# v0_6_stm32-pi.net
KiCad netlist of a schematic drawn in EAGLE
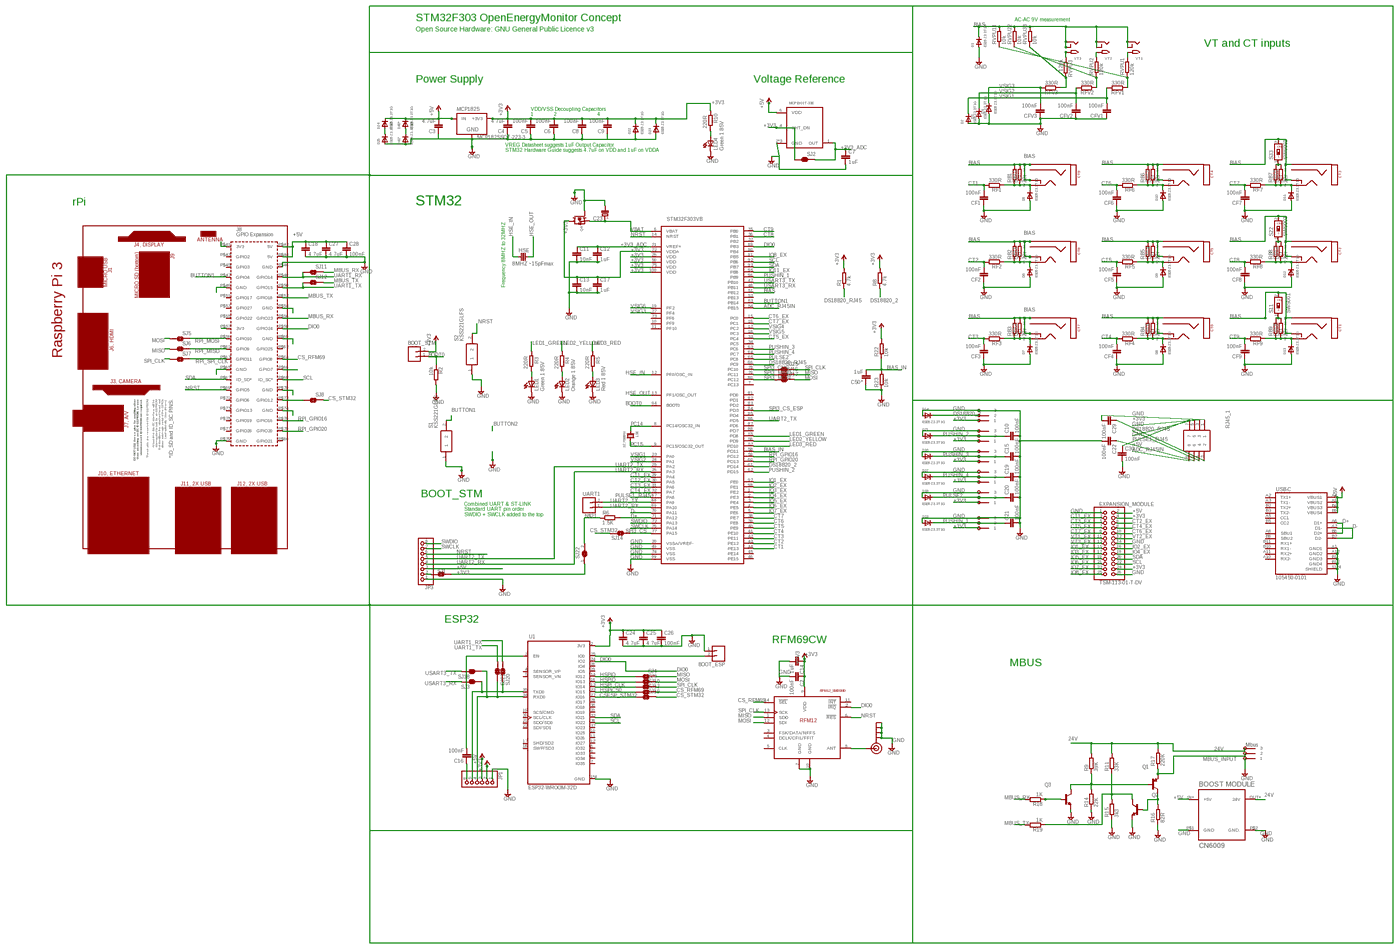
[diagram p0: schematic, sheet 1, overview]
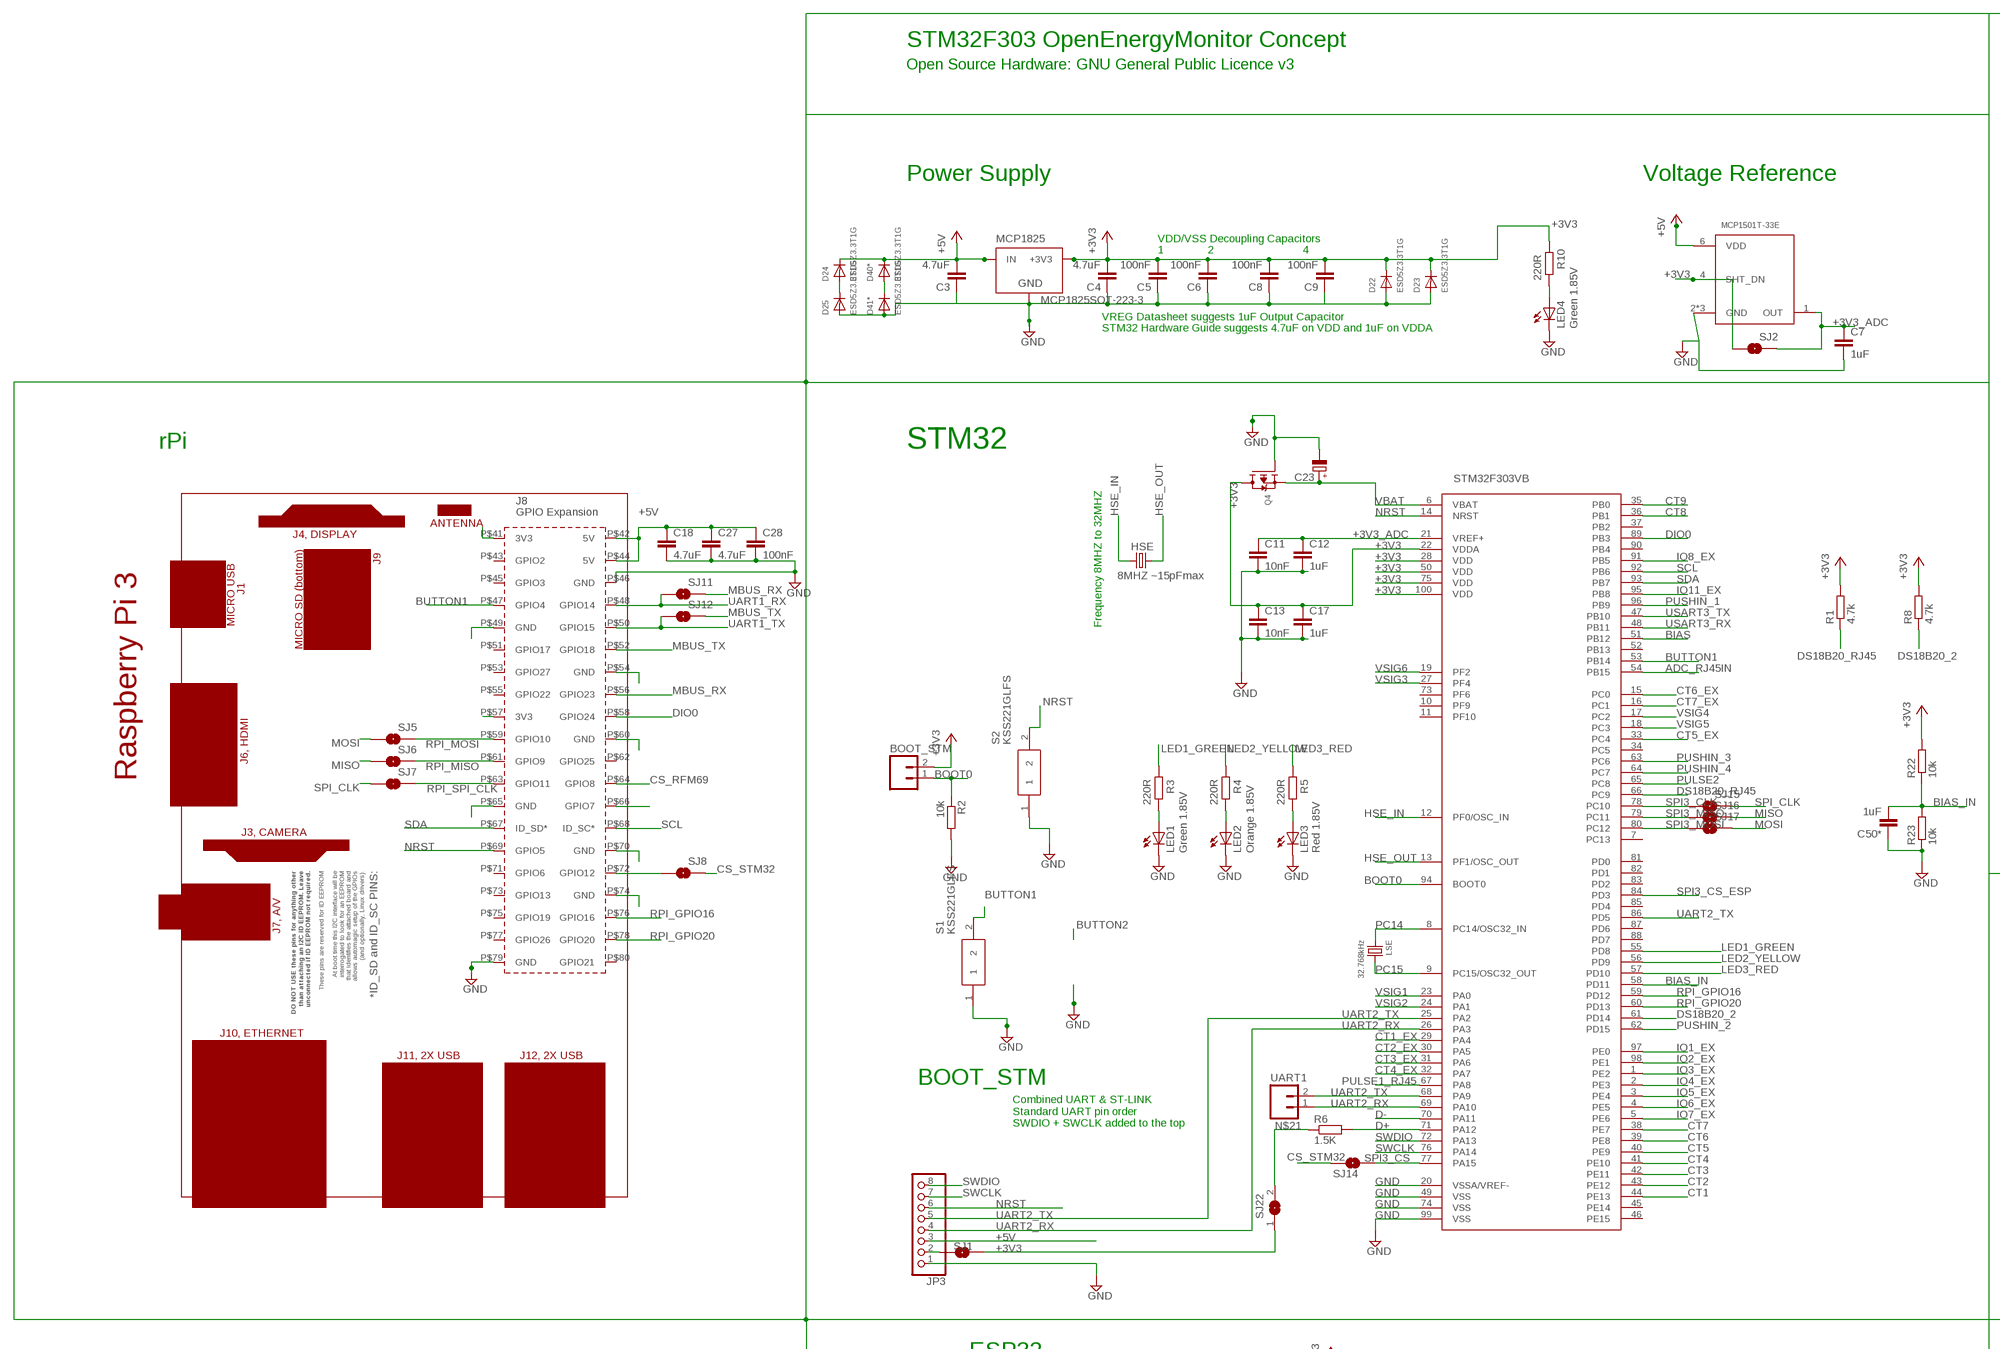
[diagram p1: schematic, sheet 1, part 1 of 4]
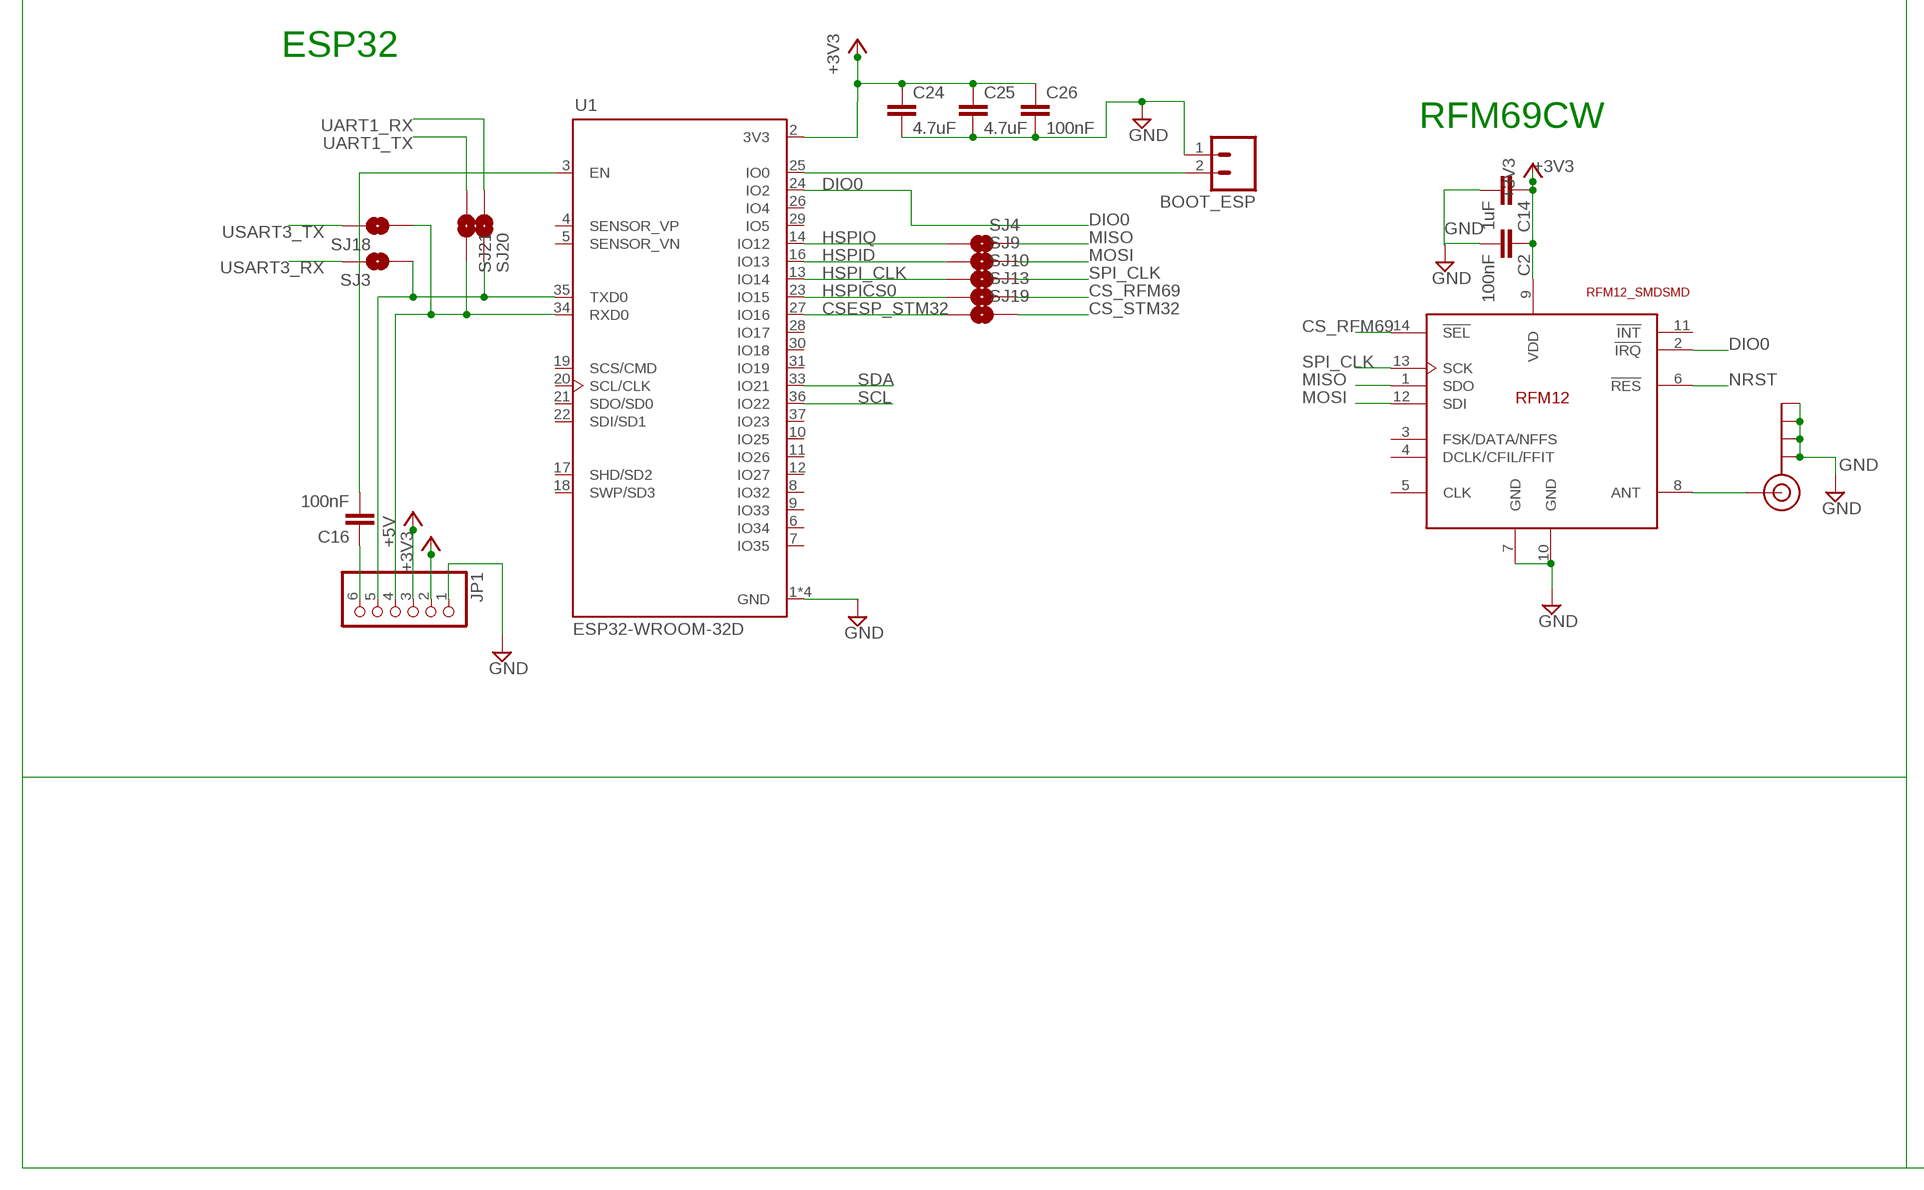
[diagram p2: schematic, sheet 1, part 2 of 4]
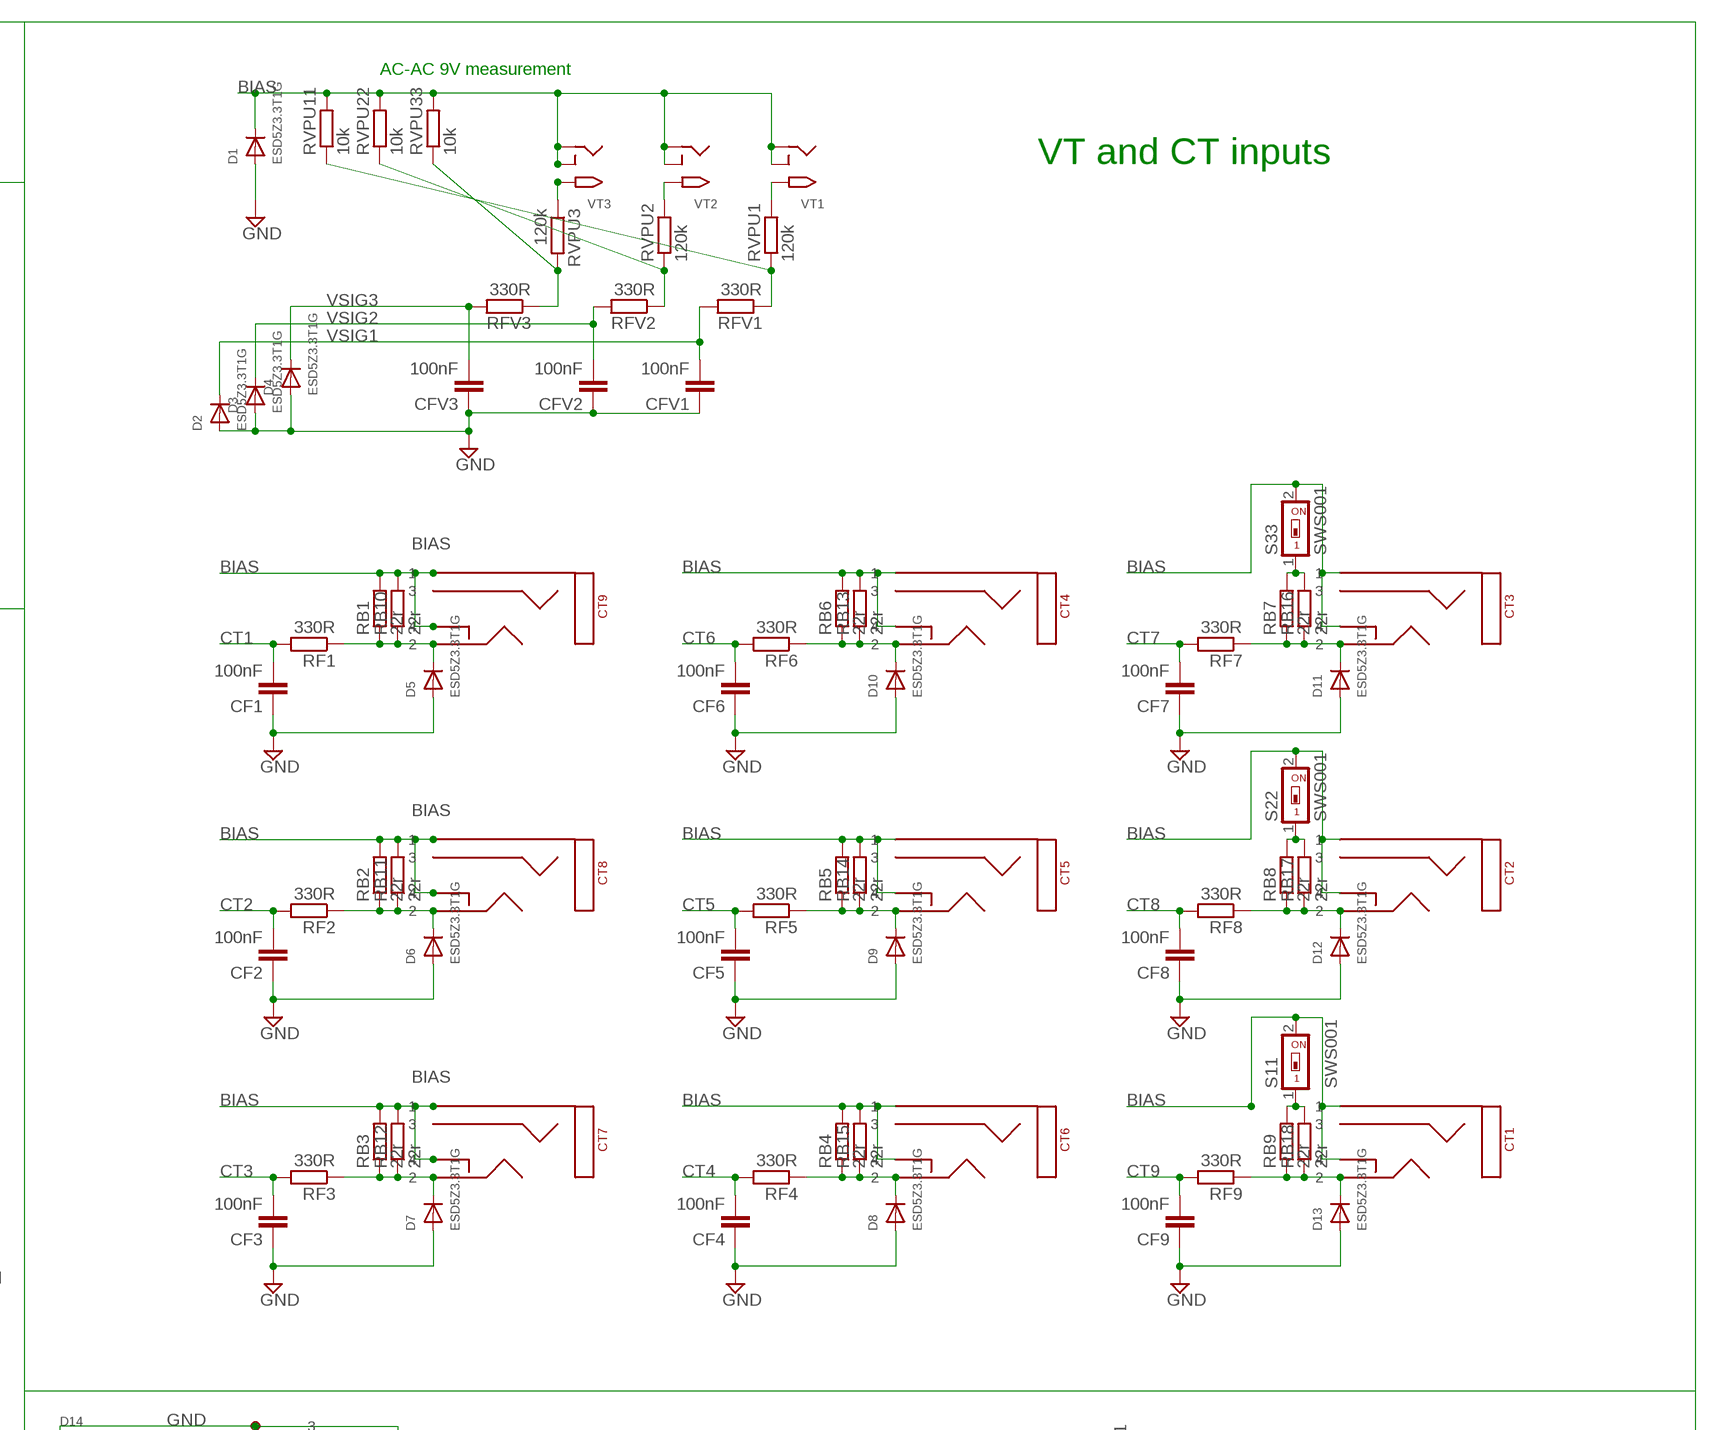
[diagram p3: schematic, sheet 1, part 3 of 4]
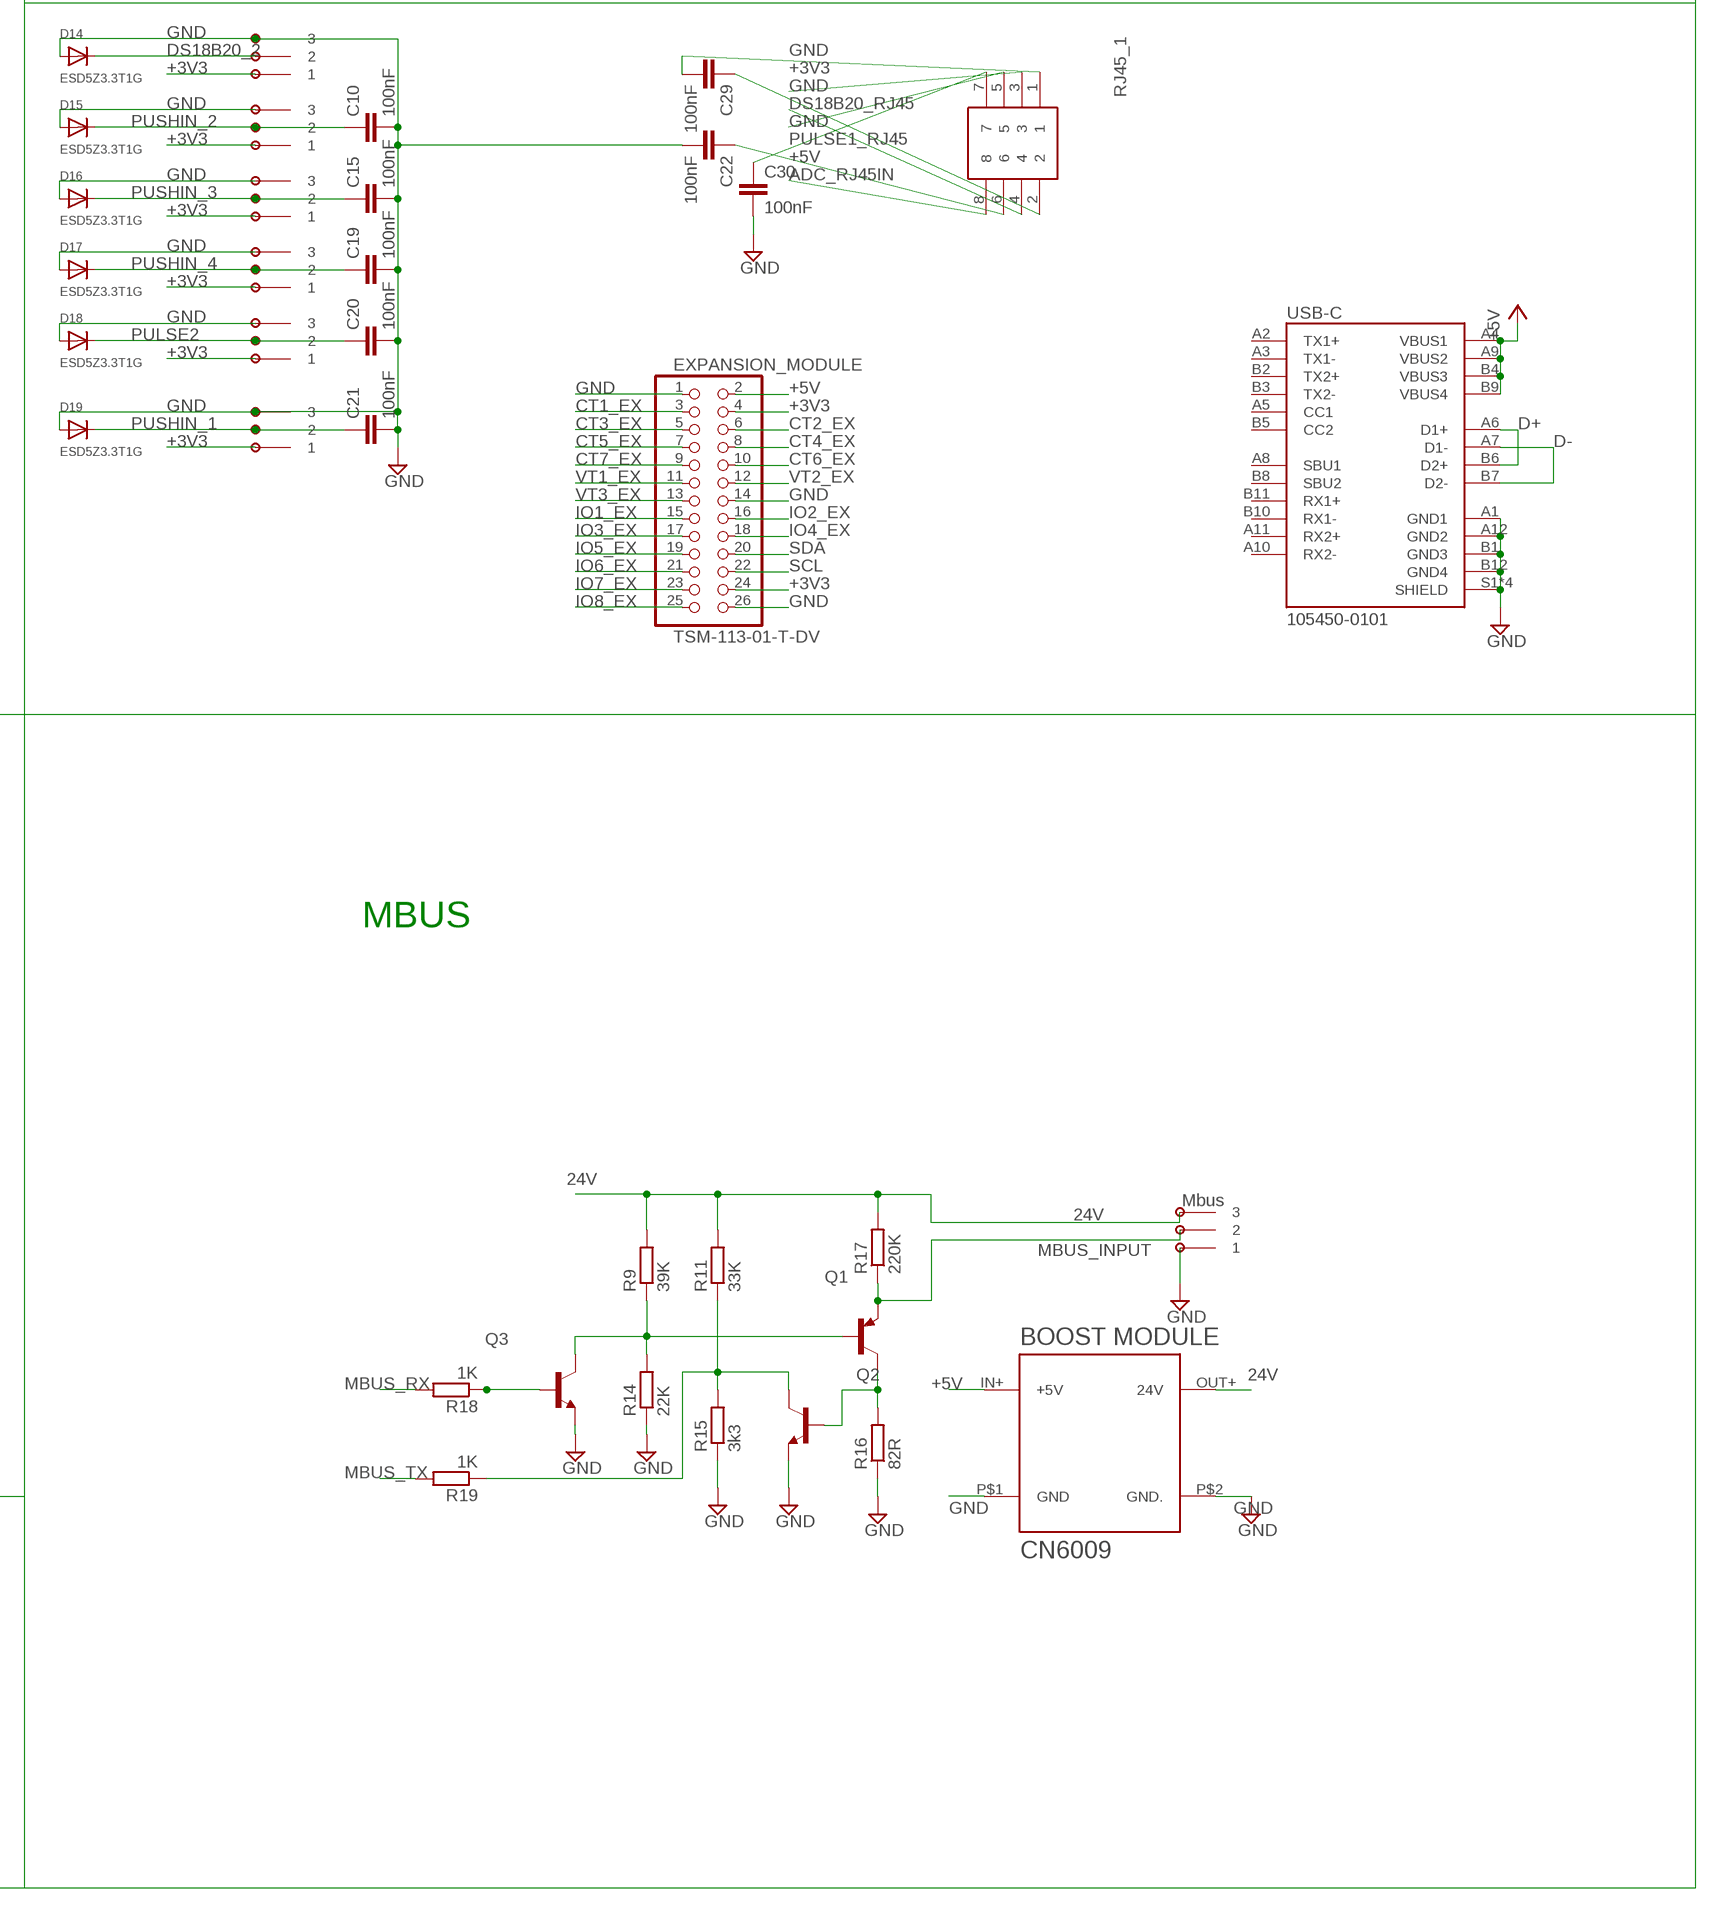
[diagram p4: schematic, sheet 1, part 4 of 4]

(export (version "E")
  (design (tool "Eeschema 10.0.6"))
  (components
    (comp (ref "3POLE_1")
      (value "OMNIMATE_LSF_3COMBICON_SMT_3")
      (footprint "eagle-import:OMNIMATE_LSF_3_SMT")
      (libsource (lib "eagle-import") (part "OMNIMATE_LSF_3COMBICON_SMT_3"))
    )
    (comp (ref "3POLE_2")
      (value "OMNIMATE_LSF_3COMBICON_SMT_3")
      (footprint "eagle-import:OMNIMATE_LSF_3_SMT")
      (libsource (lib "eagle-import") (part "OMNIMATE_LSF_3COMBICON_SMT_3"))
    )
    (comp (ref "3POLE_3")
      (value "OMNIMATE_LSF_3COMBICON_SMT_3")
      (footprint "eagle-import:OMNIMATE_LSF_3_SMT")
      (libsource (lib "eagle-import") (part "OMNIMATE_LSF_3COMBICON_SMT_3"))
    )
    (comp (ref "3POLE_4")
      (value "OMNIMATE_LSF_3COMBICON_SMT_3")
      (footprint "eagle-import:OMNIMATE_LSF_3_SMT")
      (libsource (lib "eagle-import") (part "OMNIMATE_LSF_3COMBICON_SMT_3"))
    )
    (comp (ref "3POLE_5")
      (value "OMNIMATE_LSF_3COMBICON_SMT_3")
      (footprint "eagle-import:OMNIMATE_LSF_3_SMT")
      (libsource (lib "eagle-import") (part "OMNIMATE_LSF_3COMBICON_SMT_3"))
    )
    (comp (ref "3POLE_6")
      (value "OMNIMATE_LSF_3COMBICON_SMT_3")
      (footprint "eagle-import:OMNIMATE_LSF_3_SMT")
      (libsource (lib "eagle-import") (part "OMNIMATE_LSF_3COMBICON_SMT_3"))
    )
    (comp (ref "3POLE_7")
      (value "OMNIMATE_LSF_3COMBICON_SMT_3")
      (footprint "eagle-import:OMNIMATE_LSF_3_SMT")
      (libsource (lib "eagle-import") (part "OMNIMATE_LSF_3COMBICON_SMT_3"))
    )
    (comp (ref "BOOT_ESP")
      (value "M02PTH")
      (footprint "eagle-import:1X02")
      (libsource (lib "eagle-import") (part "M02PTH"))
    )
    (comp (ref "BOOT_STM")
      (value "M02PTH")
      (footprint "eagle-import:1X02")
      (libsource (lib "eagle-import") (part "M02PTH"))
    )
    (comp (ref "C2")
      (value "100nF")
      (footprint "eagle-import:C0603")
      (libsource (lib "eagle-import") (part "resistor_C-EUC0603"))
    )
    (comp (ref "C3")
      (value "4.7uF")
      (footprint "eagle-import:C0805")
      (libsource (lib "eagle-import") (part "C-EUC0805"))
    )
    (comp (ref "C4")
      (value "4.7uF")
      (footprint "eagle-import:C0805")
      (libsource (lib "eagle-import") (part "C-EUC0805"))
    )
    (comp (ref "C5")
      (value "100nF")
      (footprint "eagle-import:C0603")
      (libsource (lib "eagle-import") (part "resistor_C-EUC0603"))
    )
    (comp (ref "C6")
      (value "100nF")
      (footprint "eagle-import:C0603")
      (libsource (lib "eagle-import") (part "resistor_C-EUC0603"))
    )
    (comp (ref "C7")
      (value "1uF")
      (footprint "eagle-import:C0805")
      (libsource (lib "eagle-import") (part "C-EUC0805"))
    )
    (comp (ref "C8")
      (value "100nF")
      (footprint "eagle-import:C0603")
      (libsource (lib "eagle-import") (part "resistor_C-EUC0603"))
    )
    (comp (ref "C9")
      (value "100nF")
      (footprint "eagle-import:C0603")
      (libsource (lib "eagle-import") (part "resistor_C-EUC0603"))
    )
    (comp (ref "C10")
      (value "100nF")
      (footprint "eagle-import:C0603")
      (libsource (lib "eagle-import") (part "resistor_C-EUC0603"))
    )
    (comp (ref "C11")
      (value "10nF")
      (footprint "eagle-import:C0603")
      (libsource (lib "eagle-import") (part "C-EUC0603"))
    )
    (comp (ref "C12")
      (value "1uF")
      (footprint "eagle-import:C0805")
      (libsource (lib "eagle-import") (part "C-EUC0805"))
    )
    (comp (ref "C13")
      (value "10nF")
      (footprint "eagle-import:C0603")
      (libsource (lib "eagle-import") (part "C-EUC0603"))
    )
    (comp (ref "C14")
      (value "1uF")
      (footprint "eagle-import:C0805")
      (libsource (lib "eagle-import") (part "C-EUC0805"))
    )
    (comp (ref "C15")
      (value "100nF")
      (footprint "eagle-import:C0603")
      (libsource (lib "eagle-import") (part "resistor_C-EUC0603"))
    )
    (comp (ref "C16")
      (value "100nF")
      (footprint "eagle-import:C0603")
      (libsource (lib "eagle-import") (part "resistor_C-EUC0603"))
    )
    (comp (ref "C17")
      (value "1uF")
      (footprint "eagle-import:C0805")
      (libsource (lib "eagle-import") (part "C-EUC0805"))
    )
    (comp (ref "C18")
      (value "4.7uF")
      (footprint "eagle-import:C0805")
      (libsource (lib "eagle-import") (part "C-EUC0805"))
    )
    (comp (ref "C19")
      (value "100nF")
      (footprint "eagle-import:C0603")
      (libsource (lib "eagle-import") (part "resistor_C-EUC0603"))
    )
    (comp (ref "C20")
      (value "100nF")
      (footprint "eagle-import:C0603")
      (libsource (lib "eagle-import") (part "resistor_C-EUC0603"))
    )
    (comp (ref "C21")
      (value "100nF")
      (footprint "eagle-import:C0603")
      (libsource (lib "eagle-import") (part "resistor_C-EUC0603"))
    )
    (comp (ref "C22")
      (value "100nF")
      (footprint "eagle-import:C0603")
      (libsource (lib "eagle-import") (part "resistor_C-EUC0603"))
    )
    (comp (ref "C23")
      (value "CPOL-EU153CLV-1010")
      (footprint "eagle-import:153CLV-1010")
      (libsource (lib "eagle-import") (part "CPOL-EU153CLV-1010"))
    )
    (comp (ref "C24")
      (value "4.7uF")
      (footprint "eagle-import:C0805")
      (libsource (lib "eagle-import") (part "C-EUC0805"))
    )
    (comp (ref "C25")
      (value "4.7uF")
      (footprint "eagle-import:C0805")
      (libsource (lib "eagle-import") (part "C-EUC0805"))
    )
    (comp (ref "C26")
      (value "100nF")
      (footprint "eagle-import:C0603")
      (libsource (lib "eagle-import") (part "resistor_C-EUC0603"))
    )
    (comp (ref "C27")
      (value "4.7uF")
      (footprint "eagle-import:C0805")
      (libsource (lib "eagle-import") (part "C-EUC0805"))
    )
    (comp (ref "C28")
      (value "100nF")
      (footprint "eagle-import:C0603")
      (libsource (lib "eagle-import") (part "resistor_C-EUC0603"))
    )
    (comp (ref "C29")
      (value "100nF")
      (footprint "eagle-import:C0603")
      (libsource (lib "eagle-import") (part "resistor_C-EUC0603"))
    )
    (comp (ref "C30")
      (value "100nF")
      (footprint "eagle-import:C0603")
      (libsource (lib "eagle-import") (part "resistor_C-EUC0603"))
    )
    (comp (ref "C50*")
      (value "1uF")
      (footprint "eagle-import:C0603")
      (libsource (lib "eagle-import") (part "C-EUC0603"))
    )
    (comp (ref "CF1")
      (value "100nF")
      (footprint "eagle-import:C0603")
      (libsource (lib "eagle-import") (part "resistor_C-EUC0603"))
    )
    (comp (ref "CF2")
      (value "100nF")
      (footprint "eagle-import:C0603")
      (libsource (lib "eagle-import") (part "resistor_C-EUC0603"))
    )
    (comp (ref "CF3")
      (value "100nF")
      (footprint "eagle-import:C0603")
      (libsource (lib "eagle-import") (part "resistor_C-EUC0603"))
    )
    (comp (ref "CF4")
      (value "100nF")
      (footprint "eagle-import:C0603")
      (libsource (lib "eagle-import") (part "resistor_C-EUC0603"))
    )
    (comp (ref "CF5")
      (value "100nF")
      (footprint "eagle-import:C0603")
      (libsource (lib "eagle-import") (part "resistor_C-EUC0603"))
    )
    (comp (ref "CF6")
      (value "100nF")
      (footprint "eagle-import:C0603")
      (libsource (lib "eagle-import") (part "resistor_C-EUC0603"))
    )
    (comp (ref "CF7")
      (value "100nF")
      (footprint "eagle-import:C0603")
      (libsource (lib "eagle-import") (part "resistor_C-EUC0603"))
    )
    (comp (ref "CF8")
      (value "100nF")
      (footprint "eagle-import:C0603")
      (libsource (lib "eagle-import") (part "resistor_C-EUC0603"))
    )
    (comp (ref "CF9")
      (value "100nF")
      (footprint "eagle-import:C0603")
      (libsource (lib "eagle-import") (part "resistor_C-EUC0603"))
    )
    (comp (ref "CFV1")
      (value "100nF")
      (footprint "eagle-import:C0603")
      (libsource (lib "eagle-import") (part "resistor_C-EUC0603"))
    )
    (comp (ref "CFV2")
      (value "100nF")
      (footprint "eagle-import:C0603")
      (libsource (lib "eagle-import") (part "resistor_C-EUC0603"))
    )
    (comp (ref "CFV3")
      (value "100nF")
      (footprint "eagle-import:C0603")
      (libsource (lib "eagle-import") (part "resistor_C-EUC0603"))
    )
    (comp (ref "CT1")
      (value "STEREO_SMD")
      (footprint "eagle-import:STEREO_SMT")
      (libsource (lib "eagle-import") (part "STEREO_SMD"))
    )
    (comp (ref "CT2")
      (value "STEREO_SMD")
      (footprint "eagle-import:STEREO_SMT")
      (libsource (lib "eagle-import") (part "STEREO_SMD"))
    )
    (comp (ref "CT3")
      (value "STEREO_SMD")
      (footprint "eagle-import:STEREO_SMT")
      (libsource (lib "eagle-import") (part "STEREO_SMD"))
    )
    (comp (ref "CT4")
      (value "STEREO_SMD")
      (footprint "eagle-import:STEREO_SMT")
      (libsource (lib "eagle-import") (part "STEREO_SMD"))
    )
    (comp (ref "CT5")
      (value "STEREO_SMD")
      (footprint "eagle-import:STEREO_SMT")
      (libsource (lib "eagle-import") (part "STEREO_SMD"))
    )
    (comp (ref "CT6")
      (value "STEREO_SMD")
      (footprint "eagle-import:STEREO_SMT")
      (libsource (lib "eagle-import") (part "STEREO_SMD"))
    )
    (comp (ref "CT7")
      (value "STEREO_SMD")
      (footprint "eagle-import:STEREO_SMT")
      (libsource (lib "eagle-import") (part "STEREO_SMD"))
    )
    (comp (ref "CT8")
      (value "STEREO_SMD")
      (footprint "eagle-import:STEREO_SMT")
      (libsource (lib "eagle-import") (part "STEREO_SMD"))
    )
    (comp (ref "CT9")
      (value "STEREO_SMD")
      (footprint "eagle-import:STEREO_SMT")
      (libsource (lib "eagle-import") (part "STEREO_SMD"))
    )
    (comp (ref "D1")
      (value "ESD5Z3.3T1G")
      (footprint "eagle-import:SOD-523")
      (libsource (lib "eagle-import") (part "DIODESOD-523"))
    )
    (comp (ref "D2")
      (value "ESD5Z3.3T1G")
      (footprint "eagle-import:SOD-523")
      (libsource (lib "eagle-import") (part "DIODESOD-523"))
    )
    (comp (ref "D3")
      (value "ESD5Z3.3T1G")
      (footprint "eagle-import:SOD-523")
      (libsource (lib "eagle-import") (part "DIODESOD-523"))
    )
    (comp (ref "D4")
      (value "ESD5Z3.3T1G")
      (footprint "eagle-import:SOD-523")
      (libsource (lib "eagle-import") (part "DIODESOD-523"))
    )
    (comp (ref "D5")
      (value "ESD5Z3.3T1G")
      (footprint "eagle-import:SOD-523")
      (libsource (lib "eagle-import") (part "DIODESOD-523"))
    )
    (comp (ref "D6")
      (value "ESD5Z3.3T1G")
      (footprint "eagle-import:SOD-523")
      (libsource (lib "eagle-import") (part "DIODESOD-523"))
    )
    (comp (ref "D7")
      (value "ESD5Z3.3T1G")
      (footprint "eagle-import:SOD-523")
      (libsource (lib "eagle-import") (part "DIODESOD-523"))
    )
    (comp (ref "D8")
      (value "ESD5Z3.3T1G")
      (footprint "eagle-import:SOD-523")
      (libsource (lib "eagle-import") (part "DIODESOD-523"))
    )
    (comp (ref "D9")
      (value "ESD5Z3.3T1G")
      (footprint "eagle-import:SOD-523")
      (libsource (lib "eagle-import") (part "DIODESOD-523"))
    )
    (comp (ref "D10")
      (value "ESD5Z3.3T1G")
      (footprint "eagle-import:SOD-523")
      (libsource (lib "eagle-import") (part "DIODESOD-523"))
    )
    (comp (ref "D11")
      (value "ESD5Z3.3T1G")
      (footprint "eagle-import:SOD-523")
      (libsource (lib "eagle-import") (part "DIODESOD-523"))
    )
    (comp (ref "D12")
      (value "ESD5Z3.3T1G")
      (footprint "eagle-import:SOD-523")
      (libsource (lib "eagle-import") (part "DIODESOD-523"))
    )
    (comp (ref "D13")
      (value "ESD5Z3.3T1G")
      (footprint "eagle-import:SOD-523")
      (libsource (lib "eagle-import") (part "DIODESOD-523"))
    )
    (comp (ref "D14")
      (value "ESD5Z3.3T1G")
      (footprint "eagle-import:SOD-523")
      (libsource (lib "eagle-import") (part "DIODESOD-523"))
    )
    (comp (ref "D15")
      (value "ESD5Z3.3T1G")
      (footprint "eagle-import:SOD-523")
      (libsource (lib "eagle-import") (part "DIODESOD-523"))
    )
    (comp (ref "D16")
      (value "ESD5Z3.3T1G")
      (footprint "eagle-import:SOD-523")
      (libsource (lib "eagle-import") (part "DIODESOD-523"))
    )
    (comp (ref "D17")
      (value "ESD5Z3.3T1G")
      (footprint "eagle-import:SOD-523")
      (libsource (lib "eagle-import") (part "DIODESOD-523"))
    )
    (comp (ref "D18")
      (value "ESD5Z3.3T1G")
      (footprint "eagle-import:SOD-523")
      (libsource (lib "eagle-import") (part "DIODESOD-523"))
    )
    (comp (ref "D19")
      (value "ESD5Z3.3T1G")
      (footprint "eagle-import:SOD-523")
      (libsource (lib "eagle-import") (part "DIODESOD-523"))
    )
    (comp (ref "D22")
      (value "ESD5Z3.3T1G")
      (footprint "eagle-import:SOD-523")
      (libsource (lib "eagle-import") (part "DIODESOD-523"))
    )
    (comp (ref "D23")
      (value "ESD5Z3.3T1G")
      (footprint "eagle-import:SOD-523")
      (libsource (lib "eagle-import") (part "DIODESOD-523"))
    )
    (comp (ref "D24")
      (value "ESD5Z3.3T1G")
      (footprint "eagle-import:SOD-523")
      (libsource (lib "eagle-import") (part "DIODESOD-523"))
    )
    (comp (ref "D25")
      (value "ESD5Z3.3T1G")
      (footprint "eagle-import:SOD-523")
      (libsource (lib "eagle-import") (part "DIODESOD-523"))
    )
    (comp (ref "D40*")
      (value "ESD5Z3.3T1G")
      (footprint "eagle-import:SOD-523")
      (libsource (lib "eagle-import") (part "DIODESOD-523"))
    )
    (comp (ref "D41*")
      (value "ESD5Z3.3T1G")
      (footprint "eagle-import:SOD-523")
      (libsource (lib "eagle-import") (part "DIODESOD-523"))
    )
    (comp (ref "EXPANSION_MODULE")
      (value "TSM-113-01-T-DV")
      (footprint "eagle-import:2X13_SMT")
      (libsource (lib "eagle-import") (part "PINHD-2X13SMT"))
    )
    (comp (ref "HSE")
      (value "8MHZ ~15pFmax")
      (footprint "eagle-import:CTS406")
      (libsource (lib "eagle-import") (part "CRYSTALCTS406"))
    )
    (comp (ref "J$1")
      (value "SMA_EDGE")
      (footprint "eagle-import:SMA-EDGE")
      (libsource (lib "eagle-import") (part "SMA_EDGE"))
    )
    (comp (ref "JP1")
      (value "PINHD-1X61X06_SMT")
      (footprint "eagle-import:1X06_SMT")
      (libsource (lib "eagle-import") (part "PINHD-1X61X06_SMT"))
    )
    (comp (ref "JP3")
      (value "PINHD-1X81X08_SMT")
      (footprint "eagle-import:1X08_SMT")
      (libsource (lib "eagle-import") (part "PINHD-1X81X08_SMT"))
    )
    (comp (ref "LED1")
      (value "Green 1.85V")
      (footprint "eagle-import:CHIP-LED0805")
      (libsource (lib "eagle-import") (part "LEDCHIP-LED0805"))
    )
    (comp (ref "LED2")
      (value "Orange 1.85V")
      (footprint "eagle-import:CHIP-LED0805")
      (libsource (lib "eagle-import") (part "LEDCHIP-LED0805"))
    )
    (comp (ref "LED3")
      (value "Red 1.85V")
      (footprint "eagle-import:CHIP-LED0805")
      (libsource (lib "eagle-import") (part "LEDCHIP-LED0805"))
    )
    (comp (ref "LED4")
      (value "Green 1.85V")
      (footprint "eagle-import:CHIP-LED0805")
      (libsource (lib "eagle-import") (part "LEDCHIP-LED0805"))
    )
    (comp (ref "LSE")
      (value "32.768kHz")
      (footprint "eagle-import:CRYSTAL_8X3.8")
      (libsource (lib "eagle-import") (part "CRYSTAL8X3.8SMT"))
    )
    (comp (ref "MCP1825")
      (value "MCP1825SOT-223-3")
      (footprint "eagle-import:SOT-223")
      (libsource (lib "eagle-import") (part "MCP1825SOT-223-3"))
    )
    (comp (ref "PCB2")
      (value "RPI3YA")
      (footprint "eagle-import:RPI3MIRROR2")
      (libsource (lib "eagle-import") (part "RPI3YA"))
    )
    (comp (ref "Q1")
      (value "MMBT3906")
      (footprint "eagle-import:SOT23")
      (fields
        (field (name "DIGIKEY_PART_NUMBER") "MMBT3906FSCT-ND")
        (field (name "MANUFACTURER") "ON Semiconductor")
        (field (name "CREATED_BY") "PCB Layout")
      )
      (libsource (lib "eagle-import") (part "MMBT3906"))
    )
    (comp (ref "Q2")
      (value "MMBT3904")
      (footprint "eagle-import:SOT23")
      (fields
        (field (name "DIGIKEY_PART_NUMBER") "MMBT3904FSCT-ND")
        (field (name "MANUFACTURER") "ON Semiconductor")
        (field (name "CREATED_BY") "PCB Layout")
      )
      (libsource (lib "eagle-import") (part "MMBT3904"))
    )
    (comp (ref "Q3")
      (value "MMBT3904")
      (footprint "eagle-import:SOT23")
      (fields
        (field (name "DIGIKEY_PART_NUMBER") "MMBT3904FSCT-ND")
        (field (name "MANUFACTURER") "ON Semiconductor")
        (field (name "CREATED_BY") "PCB Layout")
      )
      (libsource (lib "eagle-import") (part "MMBT3904"))
    )
    (comp (ref "Q4")
      (value "MOSFET-P")
      (footprint "eagle-import:SOT23-R")
      (libsource (lib "eagle-import") (part "MOSFET-P"))
    )
    (comp (ref "R1")
      (value "4.7k")
      (footprint "eagle-import:R0603")
      (libsource (lib "eagle-import") (part "resistor_R-EU_R0603"))
    )
    (comp (ref "R2")
      (value "10k")
      (footprint "eagle-import:R0603")
      (libsource (lib "eagle-import") (part "resistor_R-EU_R0603"))
    )
    (comp (ref "R3")
      (value "220R")
      (footprint "eagle-import:R0603")
      (libsource (lib "eagle-import") (part "R-EU_R0603"))
    )
    (comp (ref "R4")
      (value "220R")
      (footprint "eagle-import:R0603")
      (libsource (lib "eagle-import") (part "R-EU_R0603"))
    )
    (comp (ref "R5")
      (value "220R")
      (footprint "eagle-import:R0603")
      (libsource (lib "eagle-import") (part "R-EU_R0603"))
    )
    (comp (ref "R6")
      (value "1.5K")
      (footprint "eagle-import:R0603")
      (libsource (lib "eagle-import") (part "R-EU_R0603"))
    )
    (comp (ref "R8")
      (value "4.7k")
      (footprint "eagle-import:R0603")
      (libsource (lib "eagle-import") (part "resistor_R-EU_R0603"))
    )
    (comp (ref "R9")
      (value "39K")
      (footprint "eagle-import:R0603")
      (libsource (lib "eagle-import") (part "R-EU_R0603"))
    )
    (comp (ref "R10")
      (value "220R")
      (footprint "eagle-import:R0603")
      (libsource (lib "eagle-import") (part "R-EU_R0603"))
    )
    (comp (ref "R11")
      (value "33K")
      (footprint "eagle-import:R0603")
      (libsource (lib "eagle-import") (part "R-EU_R0603"))
    )
    (comp (ref "R14")
      (value "22K")
      (footprint "eagle-import:R0603")
      (libsource (lib "eagle-import") (part "R-EU_R0603"))
    )
    (comp (ref "R15")
      (value "3k3")
      (footprint "eagle-import:R0603")
      (libsource (lib "eagle-import") (part "R-EU_R0603"))
    )
    (comp (ref "R16")
      (value "82R")
      (footprint "eagle-import:R0603")
      (libsource (lib "eagle-import") (part "R-EU_R0603"))
    )
    (comp (ref "R17")
      (value "220K")
      (footprint "eagle-import:R0603")
      (libsource (lib "eagle-import") (part "R-EU_R0603"))
    )
    (comp (ref "R18")
      (value "1K")
      (footprint "eagle-import:R0603")
      (libsource (lib "eagle-import") (part "R-EU_R0603"))
    )
    (comp (ref "R19")
      (value "1K")
      (footprint "eagle-import:R0603")
      (libsource (lib "eagle-import") (part "R-EU_R0603"))
    )
    (comp (ref "R22")
      (value "10k")
      (footprint "eagle-import:R0603")
      (libsource (lib "eagle-import") (part "resistor_R-EU_R0603"))
    )
    (comp (ref "R23")
      (value "10k")
      (footprint "eagle-import:R0603")
      (libsource (lib "eagle-import") (part "resistor_R-EU_R0603"))
    )
    (comp (ref "RB1")
      (value "22r")
      (footprint "eagle-import:R0603")
      (libsource (lib "eagle-import") (part "resistor_R-EU_R0603"))
    )
    (comp (ref "RB2")
      (value "22r")
      (footprint "eagle-import:R0603")
      (libsource (lib "eagle-import") (part "resistor_R-EU_R0603"))
    )
    (comp (ref "RB3")
      (value "22r")
      (footprint "eagle-import:R0603")
      (libsource (lib "eagle-import") (part "resistor_R-EU_R0603"))
    )
    (comp (ref "RB4")
      (value "22r")
      (footprint "eagle-import:R0603")
      (libsource (lib "eagle-import") (part "resistor_R-EU_R0603"))
    )
    (comp (ref "RB5")
      (value "22r")
      (footprint "eagle-import:R0603")
      (libsource (lib "eagle-import") (part "resistor_R-EU_R0603"))
    )
    (comp (ref "RB6")
      (value "22r")
      (footprint "eagle-import:R0603")
      (libsource (lib "eagle-import") (part "resistor_R-EU_R0603"))
    )
    (comp (ref "RB7")
      (value "22r")
      (footprint "eagle-import:R0603")
      (libsource (lib "eagle-import") (part "resistor_R-EU_R0603"))
    )
    (comp (ref "RB8")
      (value "22r")
      (footprint "eagle-import:R0603")
      (libsource (lib "eagle-import") (part "resistor_R-EU_R0603"))
    )
    (comp (ref "RB9")
      (value "22r")
      (footprint "eagle-import:R0603")
      (libsource (lib "eagle-import") (part "resistor_R-EU_R0603"))
    )
    (comp (ref "RB10")
      (value "22r")
      (footprint "eagle-import:0207_7")
      (libsource (lib "eagle-import") (part "R-EU_0207/7"))
    )
    (comp (ref "RB11")
      (value "22r")
      (footprint "eagle-import:0207_7")
      (libsource (lib "eagle-import") (part "R-EU_0207/7"))
    )
    (comp (ref "RB12")
      (value "22r")
      (footprint "eagle-import:0207_7")
      (libsource (lib "eagle-import") (part "R-EU_0207/7"))
    )
    (comp (ref "RB13")
      (value "22r")
      (footprint "eagle-import:0207_7")
      (libsource (lib "eagle-import") (part "R-EU_0207/7"))
    )
    (comp (ref "RB14")
      (value "22r")
      (footprint "eagle-import:0207_7")
      (libsource (lib "eagle-import") (part "R-EU_0207/7"))
    )
    (comp (ref "RB15")
      (value "22r")
      (footprint "eagle-import:0207_7")
      (libsource (lib "eagle-import") (part "R-EU_0207/7"))
    )
    (comp (ref "RB16")
      (value "22r")
      (footprint "eagle-import:0207_7")
      (libsource (lib "eagle-import") (part "R-EU_0207/7"))
    )
    (comp (ref "RB17")
      (value "22r")
      (footprint "eagle-import:0207_7")
      (libsource (lib "eagle-import") (part "R-EU_0207/7"))
    )
    (comp (ref "RB18")
      (value "22r")
      (footprint "eagle-import:0207_7")
      (libsource (lib "eagle-import") (part "R-EU_0207/7"))
    )
    (comp (ref "RF1")
      (value "330R")
      (footprint "eagle-import:R0603")
      (libsource (lib "eagle-import") (part "resistor_R-EU_R0603"))
    )
    (comp (ref "RF2")
      (value "330R")
      (footprint "eagle-import:R0603")
      (libsource (lib "eagle-import") (part "resistor_R-EU_R0603"))
    )
    (comp (ref "RF3")
      (value "330R")
      (footprint "eagle-import:R0603")
      (libsource (lib "eagle-import") (part "resistor_R-EU_R0603"))
    )
    (comp (ref "RF4")
      (value "330R")
      (footprint "eagle-import:R0603")
      (libsource (lib "eagle-import") (part "resistor_R-EU_R0603"))
    )
    (comp (ref "RF5")
      (value "330R")
      (footprint "eagle-import:R0603")
      (libsource (lib "eagle-import") (part "resistor_R-EU_R0603"))
    )
    (comp (ref "RF6")
      (value "330R")
      (footprint "eagle-import:R0603")
      (libsource (lib "eagle-import") (part "resistor_R-EU_R0603"))
    )
    (comp (ref "RF7")
      (value "330R")
      (footprint "eagle-import:R0603")
      (libsource (lib "eagle-import") (part "resistor_R-EU_R0603"))
    )
    (comp (ref "RF8")
      (value "330R")
      (footprint "eagle-import:R0603")
      (libsource (lib "eagle-import") (part "resistor_R-EU_R0603"))
    )
    (comp (ref "RF9")
      (value "330R")
      (footprint "eagle-import:R0603")
      (libsource (lib "eagle-import") (part "resistor_R-EU_R0603"))
    )
    (comp (ref "RFM69HCW")
      (value "RFM12_SMDSMD")
      (footprint "eagle-import:RFM12")
      (libsource (lib "eagle-import") (part "RFM12_SMDSMD"))
    )
    (comp (ref "RFV1")
      (value "330R")
      (footprint "eagle-import:R0603")
      (libsource (lib "eagle-import") (part "resistor_R-EU_R0603"))
    )
    (comp (ref "RFV2")
      (value "330R")
      (footprint "eagle-import:R0603")
      (libsource (lib "eagle-import") (part "resistor_R-EU_R0603"))
    )
    (comp (ref "RFV3")
      (value "330R")
      (footprint "eagle-import:R0603")
      (libsource (lib "eagle-import") (part "resistor_R-EU_R0603"))
    )
    (comp (ref "RJ45_1")
      (value "95501-6889")
      (footprint "eagle-import:955016889")
      (fields (field (name "MOUSER_PART_NUMBER") "538-95501-6889") (field (name "RS_PART_NUMBER") "3862738"))
      (libsource (lib "eagle-import") (part "95501-6889"))
    )
    (comp (ref "RVPU1")
      (value "120k")
      (footprint "eagle-import:R0603")
      (libsource (lib "eagle-import") (part "resistor_R-EU_R0603"))
    )
    (comp (ref "RVPU2")
      (value "120k")
      (footprint "eagle-import:R0603")
      (libsource (lib "eagle-import") (part "resistor_R-EU_R0603"))
    )
    (comp (ref "RVPU3")
      (value "120k")
      (footprint "eagle-import:R0603")
      (libsource (lib "eagle-import") (part "resistor_R-EU_R0603"))
    )
    (comp (ref "RVPU11")
      (value "10k")
      (footprint "eagle-import:R0603")
      (libsource (lib "eagle-import") (part "resistor_R-EU_R0603"))
    )
    (comp (ref "RVPU22")
      (value "10k")
      (footprint "eagle-import:R0603")
      (libsource (lib "eagle-import") (part "resistor_R-EU_R0603"))
    )
    (comp (ref "RVPU33")
      (value "10k")
      (footprint "eagle-import:R0603")
      (libsource (lib "eagle-import") (part "resistor_R-EU_R0603"))
    )
    (comp (ref "S1")
      (value "KSS221GLFS")
      (footprint "eagle-import:KSS")
      (fields (field (name "RS_PART_NUMBER") "7931689P"))
      (libsource (lib "eagle-import") (part "KSS221GLFS"))
    )
    (comp (ref "S2")
      (value "KSS221GLFS")
      (footprint "eagle-import:KSS")
      (fields (field (name "RS_PART_NUMBER") "7931689P"))
      (libsource (lib "eagle-import") (part "KSS221GLFS"))
    )
    (comp (ref "S11")
      (value "SWS001")
      (footprint "eagle-import:SMS-001")
      (libsource (lib "eagle-import") (part "SWS001"))
    )
    (comp (ref "S22")
      (value "SWS001")
      (footprint "eagle-import:SMS-001")
      (libsource (lib "eagle-import") (part "SWS001"))
    )
    (comp (ref "S33")
      (value "SWS001")
      (footprint "eagle-import:SMS-001")
      (libsource (lib "eagle-import") (part "SWS001"))
    )
    (comp (ref "SJ1")
      (value "SOLDERJUMPERNO")
      (footprint "eagle-import:SJ_2S-NO")
      (libsource (lib "eagle-import") (part "SOLDERJUMPERNO"))
    )
    (comp (ref "SJ2")
      (value "SOLDERJUMPERNO")
      (footprint "eagle-import:SJ_2S-NO")
      (libsource (lib "eagle-import") (part "SOLDERJUMPERNO"))
    )
    (comp (ref "SJ3")
      (value "SOLDERJUMPERNO")
      (footprint "eagle-import:SJ_2S-NO")
      (libsource (lib "eagle-import") (part "SOLDERJUMPERNO"))
    )
    (comp (ref "SJ4")
      (value "SOLDERJUMPERNO")
      (footprint "eagle-import:SJ_2S-NO")
      (libsource (lib "eagle-import") (part "SOLDERJUMPERNO"))
    )
    (comp (ref "SJ5")
      (value "SOLDERJUMPERNO")
      (footprint "eagle-import:SJ_2S-NO")
      (libsource (lib "eagle-import") (part "SOLDERJUMPERNO"))
    )
    (comp (ref "SJ6")
      (value "SOLDERJUMPERNO")
      (footprint "eagle-import:SJ_2S-NO")
      (libsource (lib "eagle-import") (part "SOLDERJUMPERNO"))
    )
    (comp (ref "SJ7")
      (value "SOLDERJUMPERNO")
      (footprint "eagle-import:SJ_2S-NO")
      (libsource (lib "eagle-import") (part "SOLDERJUMPERNO"))
    )
    (comp (ref "SJ8")
      (value "SOLDERJUMPERNO")
      (footprint "eagle-import:SJ_2S-NO")
      (libsource (lib "eagle-import") (part "SOLDERJUMPERNO"))
    )
    (comp (ref "SJ9")
      (value "SOLDERJUMPERNO")
      (footprint "eagle-import:SJ_2S-NO")
      (libsource (lib "eagle-import") (part "SOLDERJUMPERNO"))
    )
    (comp (ref "SJ10")
      (value "SOLDERJUMPERNO")
      (footprint "eagle-import:SJ_2S-NO")
      (libsource (lib "eagle-import") (part "SOLDERJUMPERNO"))
    )
    (comp (ref "SJ11")
      (value "SOLDERJUMPERNO")
      (footprint "eagle-import:SJ_2S-NO")
      (libsource (lib "eagle-import") (part "SOLDERJUMPERNO"))
    )
    (comp (ref "SJ12")
      (value "SOLDERJUMPERNO")
      (footprint "eagle-import:SJ_2S-NO")
      (libsource (lib "eagle-import") (part "SOLDERJUMPERNO"))
    )
    (comp (ref "SJ13")
      (value "SOLDERJUMPERNO")
      (footprint "eagle-import:SJ_2S-NO")
      (libsource (lib "eagle-import") (part "SOLDERJUMPERNO"))
    )
    (comp (ref "SJ14")
      (value "SOLDERJUMPERNO")
      (footprint "eagle-import:SJ_2S-NO")
      (libsource (lib "eagle-import") (part "SOLDERJUMPERNO"))
    )
    (comp (ref "SJ15")
      (value "SOLDERJUMPERNO")
      (footprint "eagle-import:SJ_2S-NO")
      (libsource (lib "eagle-import") (part "SOLDERJUMPERNO"))
    )
    (comp (ref "SJ16")
      (value "SOLDERJUMPERNO")
      (footprint "eagle-import:SJ_2S-NO")
      (libsource (lib "eagle-import") (part "SOLDERJUMPERNO"))
    )
    (comp (ref "SJ17")
      (value "SOLDERJUMPERNO")
      (footprint "eagle-import:SJ_2S-NO")
      (libsource (lib "eagle-import") (part "SOLDERJUMPERNO"))
    )
    (comp (ref "SJ18")
      (value "SOLDERJUMPERNO")
      (footprint "eagle-import:SJ_2S-NO")
      (libsource (lib "eagle-import") (part "SOLDERJUMPERNO"))
    )
    (comp (ref "SJ19")
      (value "SOLDERJUMPERNO")
      (footprint "eagle-import:SJ_2S-NO")
      (libsource (lib "eagle-import") (part "SOLDERJUMPERNO"))
    )
    (comp (ref "SJ20")
      (value "SOLDERJUMPERNO")
      (footprint "eagle-import:SJ_2S-NO")
      (libsource (lib "eagle-import") (part "SOLDERJUMPERNO"))
    )
    (comp (ref "SJ21")
      (value "SOLDERJUMPERNO")
      (footprint "eagle-import:SJ_2S-NO")
      (libsource (lib "eagle-import") (part "SOLDERJUMPERNO"))
    )
    (comp (ref "SJ22")
      (value "SJ-CONCON")
      (footprint "eagle-import:SJ-CON")
      (libsource (lib "eagle-import") (part "SJ-CONCON"))
    )
    (comp (ref "STM32F303VB")
      (value "STM32F303XB")
      (footprint "eagle-import:TQFP100")
      (libsource (lib "eagle-import") (part "STM32F303XB"))
    )
    (comp (ref "U$2")
      (value "BOOST_MODULE")
      (footprint "eagle-import:BOOST")
      (libsource (lib "eagle-import") (part "BOOST_MODULE"))
    )
    (comp (ref "U1")
      (value "ESP32-WROOM-32D")
      (footprint "eagle-import:MODULE_ESP32-WROOM-32D")
      (fields (field (name "MF") "Espressif Systems"))
      (libsource (lib "eagle-import") (part "ESP32-WROOM-32D"))
    )
    (comp (ref "UART1")
      (value "M02PTH")
      (footprint "eagle-import:1X02")
      (libsource (lib "eagle-import") (part "M02PTH"))
    )
    (comp (ref "USB-C")
      (value "105450-0101")
      (footprint "eagle-import:MOLEX_105450-0101")
      (fields (field (name "MF") "Molex"))
      (libsource (lib "eagle-import") (part "105450-0101"))
    )
    (comp (ref "VREF_3V3")
      (value "MCP1501T-33E")
      (footprint "eagle-import:SOT95P280X145-6N")
      (libsource (lib "eagle-import") (part "MCP1501T-33E"))
    )
    (comp (ref "VT1")
      (value "2.1MMJACKSMT")
      (footprint "eagle-import:DCJACK_2MM_SMT")
      (libsource (lib "eagle-import") (part "2.1MMJACKSMT"))
    )
    (comp (ref "VT2")
      (value "2.1MMJACKSMT")
      (footprint "eagle-import:DCJACK_2MM_SMT")
      (libsource (lib "eagle-import") (part "2.1MMJACKSMT"))
    )
    (comp (ref "VT3")
      (value "2.1MMJACKSMT")
      (footprint "eagle-import:DCJACK_2MM_SMT")
      (libsource (lib "eagle-import") (part "2.1MMJACKSMT"))
    )
  )
  (nets
    (net (code "1") (name "+3V3") (class "Default")
      (node (ref "3POLE_1") (pin "P$1") (pinfunction "1_P$1") (pintype "bidirectional"))
      (node (ref "3POLE_2") (pin "P$1") (pinfunction "1_P$1") (pintype "bidirectional"))
      (node (ref "3POLE_3") (pin "P$1") (pinfunction "1_P$1") (pintype "bidirectional"))
      (node (ref "3POLE_4") (pin "P$1") (pinfunction "1_P$1") (pintype "bidirectional"))
      (node (ref "3POLE_5") (pin "P$1") (pinfunction "1_P$1") (pintype "bidirectional"))
      (node (ref "3POLE_6") (pin "P$1") (pinfunction "1_P$1") (pintype "bidirectional"))
      (node (ref "BOOT_STM") (pin "2") (pinfunction "2_2") (pintype "passive"))
      (node (ref "C13") (pin "1") (pinfunction "1_1") (pintype "passive"))
      (node (ref "C14") (pin "1") (pinfunction "1_1") (pintype "passive"))
      (node (ref "C17") (pin "1") (pinfunction "1_1") (pintype "passive"))
      (node (ref "C2") (pin "1") (pinfunction "1_1") (pintype "passive"))
      (node (ref "C24") (pin "1") (pinfunction "1_1") (pintype "passive"))
      (node (ref "C25") (pin "1") (pinfunction "1_1") (pintype "passive"))
      (node (ref "C26") (pin "1") (pinfunction "1_1") (pintype "passive"))
      (node (ref "C29") (pin "1") (pinfunction "1_1") (pintype "passive"))
      (node (ref "C4") (pin "2") (pinfunction "2_2") (pintype "passive"))
      (node (ref "C5") (pin "2") (pinfunction "2_2") (pintype "passive"))
      (node (ref "C6") (pin "2") (pinfunction "2_2") (pintype "passive"))
      (node (ref "C8") (pin "2") (pinfunction "2_2") (pintype "passive"))
      (node (ref "C9") (pin "2") (pinfunction "2_2") (pintype "passive"))
      (node (ref "D22") (pin "K") (pinfunction "C_K") (pintype "passive"))
      (node (ref "D23") (pin "K") (pinfunction "C_K") (pintype "passive"))
      (node (ref "EXPANSION_MODULE") (pin "24") (pinfunction "24_24") (pintype "passive"))
      (node (ref "EXPANSION_MODULE") (pin "4") (pinfunction "4_4") (pintype "passive"))
      (node (ref "JP1") (pin "2") (pinfunction "2_2") (pintype "passive"))
      (node (ref "MCP1825") (pin "3") (pinfunction "+3V3_3") (pintype "power_in"))
      (node (ref "Q4") (pin "3") (pinfunction "D_3") (pintype "passive"))
      (node (ref "R1") (pin "2") (pinfunction "2_2") (pintype "passive"))
      (node (ref "R10") (pin "2") (pinfunction "2_2") (pintype "passive"))
      (node (ref "R22") (pin "2") (pinfunction "2_2") (pintype "passive"))
      (node (ref "R8") (pin "2") (pinfunction "2_2") (pintype "passive"))
      (node (ref "RFM69HCW") (pin "9") (pinfunction "VDD_9") (pintype "power_in"))
      (node (ref "RJ45_1") (pin "2") (pinfunction "2_2") (pintype "bidirectional"))
      (node (ref "SJ1") (pin "2") (pinfunction "2_2") (pintype "passive"))
      (node (ref "SJ2") (pin "1") (pinfunction "1_1") (pintype "passive"))
      (node (ref "SJ22") (pin "1") (pinfunction "1_1") (pintype "passive"))
      (node (ref "STM32F303VB") (pin "100") (pinfunction "VDD_100") (pintype "bidirectional"))
      (node (ref "STM32F303VB") (pin "22") (pinfunction "VDDA_22") (pintype "bidirectional"))
      (node (ref "STM32F303VB") (pin "28") (pinfunction "VDD_28") (pintype "bidirectional"))
      (node (ref "STM32F303VB") (pin "50") (pinfunction "VDD_50") (pintype "bidirectional"))
      (node (ref "STM32F303VB") (pin "75") (pinfunction "VDD_75") (pintype "bidirectional"))
      (node (ref "U1") (pin "2") (pinfunction "3V3_2") (pintype "power_in"))
      (node (ref "VREF_3V3") (pin "4") (pinfunction "SHT_DN_4") (pintype "bidirectional"))
    )
    (net (code "2") (name "+5V") (class "Default")
      (node (ref "C18") (pin "1") (pinfunction "1_1") (pintype "passive"))
      (node (ref "C27") (pin "1") (pinfunction "1_1") (pintype "passive"))
      (node (ref "C28") (pin "1") (pinfunction "1_1") (pintype "passive"))
      (node (ref "C3") (pin "2") (pinfunction "2_2") (pintype "passive"))
      (node (ref "C30") (pin "1") (pinfunction "1_1") (pintype "passive"))
      (node (ref "D24") (pin "K") (pinfunction "C_K") (pintype "passive"))
      (node (ref "D40*") (pin "K") (pinfunction "C_K") (pintype "passive"))
      (node (ref "EXPANSION_MODULE") (pin "2") (pinfunction "2_2") (pintype "passive"))
      (node (ref "JP1") (pin "3") (pinfunction "3_3") (pintype "passive"))
      (node (ref "JP3") (pin "3") (pinfunction "3_3") (pintype "passive"))
      (node (ref "MCP1825") (pin "1") (pinfunction "IN_1") (pintype "power_in"))
      (node (ref "PCB2") (pin "P$42") (pinfunction "5V_P$42") (pintype "bidirectional"))
      (node (ref "PCB2") (pin "P$44") (pinfunction "5V_P$44") (pintype "bidirectional"))
      (node (ref "RJ45_1") (pin "7") (pinfunction "7_7") (pintype "bidirectional"))
      (node (ref "U$2") (pin "IN+") (pinfunction "+5V_IN+") (pintype "bidirectional"))
      (node (ref "USB-C") (pin "A4") (pinfunction "VBUS1_A4") (pintype "passive"))
      (node (ref "USB-C") (pin "A9") (pinfunction "VBUS2_A9") (pintype "passive"))
      (node (ref "USB-C") (pin "B4") (pinfunction "VBUS3_B4") (pintype "passive"))
      (node (ref "USB-C") (pin "B9") (pinfunction "VBUS4_B9") (pintype "passive"))
      (node (ref "VREF_3V3") (pin "6") (pinfunction "VDD_6") (pintype "bidirectional"))
    )
    (net (code "3") (name "/+3V3_ADC") (class "Default")
      (node (ref "C11") (pin "1") (pinfunction "1_1") (pintype "passive"))
      (node (ref "C12") (pin "1") (pinfunction "1_1") (pintype "passive"))
      (node (ref "C7") (pin "1") (pinfunction "1_1") (pintype "passive"))
      (node (ref "SJ2") (pin "2") (pinfunction "2_2") (pintype "passive"))
      (node (ref "STM32F303VB") (pin "21") (pinfunction "VREF+_21") (pintype "bidirectional"))
      (node (ref "VREF_3V3") (pin "1") (pinfunction "OUT_1") (pintype "bidirectional"))
    )
    (net (code "4") (name "/24V") (class "Default")
      (node (ref "3POLE_7") (pin "P$3") (pinfunction "3_P$3") (pintype "bidirectional"))
      (node (ref "R11") (pin "2") (pinfunction "2_2") (pintype "passive"))
      (node (ref "R17") (pin "2") (pinfunction "2_2") (pintype "passive"))
      (node (ref "R9") (pin "2") (pinfunction "2_2") (pintype "passive"))
      (node (ref "U$2") (pin "OUT+") (pinfunction "24V_OUT+") (pintype "bidirectional"))
    )
    (net (code "5") (name "/ADC_RJ45IN") (class "Default")
      (node (ref "RJ45_1") (pin "8") (pinfunction "8_8") (pintype "bidirectional"))
      (node (ref "STM32F303VB") (pin "54") (pinfunction "PB15_54") (pintype "bidirectional"))
    )
    (net (code "6") (name "/BIAS") (class "Default")
      (node (ref "CT1") (pin "P$1") (pinfunction "1_P$1") (pintype "bidirectional"))
      (node (ref "CT1") (pin "P$4") (pinfunction "4_P$4") (pintype "bidirectional"))
      (node (ref "CT2") (pin "P$1") (pinfunction "1_P$1") (pintype "bidirectional"))
      (node (ref "CT2") (pin "P$4") (pinfunction "4_P$4") (pintype "bidirectional"))
      (node (ref "CT3") (pin "P$1") (pinfunction "1_P$1") (pintype "bidirectional"))
      (node (ref "CT3") (pin "P$4") (pinfunction "4_P$4") (pintype "bidirectional"))
      (node (ref "CT4") (pin "P$1") (pinfunction "1_P$1") (pintype "bidirectional"))
      (node (ref "CT4") (pin "P$4") (pinfunction "4_P$4") (pintype "bidirectional"))
      (node (ref "CT5") (pin "P$1") (pinfunction "1_P$1") (pintype "bidirectional"))
      (node (ref "CT5") (pin "P$4") (pinfunction "4_P$4") (pintype "bidirectional"))
      (node (ref "CT6") (pin "P$1") (pinfunction "1_P$1") (pintype "bidirectional"))
      (node (ref "CT6") (pin "P$4") (pinfunction "4_P$4") (pintype "bidirectional"))
      (node (ref "CT7") (pin "P$1") (pinfunction "1_P$1") (pintype "bidirectional"))
      (node (ref "CT7") (pin "P$4") (pinfunction "4_P$4") (pintype "bidirectional"))
      (node (ref "CT8") (pin "P$1") (pinfunction "1_P$1") (pintype "bidirectional"))
      (node (ref "CT8") (pin "P$4") (pinfunction "4_P$4") (pintype "bidirectional"))
      (node (ref "CT9") (pin "P$1") (pinfunction "1_P$1") (pintype "bidirectional"))
      (node (ref "CT9") (pin "P$4") (pinfunction "4_P$4") (pintype "bidirectional"))
      (node (ref "D1") (pin "K") (pinfunction "C_K") (pintype "passive"))
      (node (ref "RB1") (pin "2") (pinfunction "2_2") (pintype "passive"))
      (node (ref "RB10") (pin "2") (pinfunction "2_2") (pintype "passive"))
      (node (ref "RB11") (pin "2") (pinfunction "2_2") (pintype "passive"))
      (node (ref "RB12") (pin "2") (pinfunction "2_2") (pintype "passive"))
      (node (ref "RB13") (pin "2") (pinfunction "2_2") (pintype "passive"))
      (node (ref "RB14") (pin "2") (pinfunction "2_2") (pintype "passive"))
      (node (ref "RB15") (pin "2") (pinfunction "2_2") (pintype "passive"))
      (node (ref "RB2") (pin "2") (pinfunction "2_2") (pintype "passive"))
      (node (ref "RB3") (pin "2") (pinfunction "2_2") (pintype "passive"))
      (node (ref "RB4") (pin "2") (pinfunction "2_2") (pintype "passive"))
      (node (ref "RB5") (pin "2") (pinfunction "2_2") (pintype "passive"))
      (node (ref "RB6") (pin "2") (pinfunction "2_2") (pintype "passive"))
      (node (ref "RVPU11") (pin "2") (pinfunction "2_2") (pintype "passive"))
      (node (ref "RVPU22") (pin "2") (pinfunction "2_2") (pintype "passive"))
      (node (ref "RVPU33") (pin "2") (pinfunction "2_2") (pintype "passive"))
      (node (ref "S11") (pin "2") (pinfunction "2_2") (pintype "passive"))
      (node (ref "S22") (pin "2") (pinfunction "2_2") (pintype "passive"))
      (node (ref "S33") (pin "2") (pinfunction "2_2") (pintype "passive"))
      (node (ref "STM32F303VB") (pin "51") (pinfunction "PB12_51") (pintype "bidirectional"))
      (node (ref "VT1") (pin "GND") (pinfunction "RING_GND") (pintype "bidirectional"))
      (node (ref "VT1") (pin "GNDBREAK") (pinfunction "RING_SW_GNDBREAK") (pintype "bidirectional"))
      (node (ref "VT2") (pin "GND") (pinfunction "RING_GND") (pintype "bidirectional"))
      (node (ref "VT2") (pin "GNDBREAK") (pinfunction "RING_SW_GNDBREAK") (pintype "bidirectional"))
      (node (ref "VT3") (pin "GND") (pinfunction "RING_GND") (pintype "bidirectional"))
      (node (ref "VT3") (pin "GNDBREAK") (pinfunction "RING_SW_GNDBREAK") (pintype "bidirectional"))
    )
    (net (code "7") (name "/BIAS_IN") (class "Default")
      (node (ref "C50*") (pin "2") (pinfunction "2_2") (pintype "passive"))
      (node (ref "R22") (pin "1") (pinfunction "1_1") (pintype "passive"))
      (node (ref "R23") (pin "2") (pinfunction "2_2") (pintype "passive"))
      (node (ref "STM32F303VB") (pin "58") (pinfunction "PD11_58") (pintype "bidirectional"))
    )
    (net (code "8") (name "/BOOT0") (class "Default")
      (node (ref "BOOT_STM") (pin "1") (pinfunction "1_1") (pintype "passive"))
      (node (ref "R2") (pin "1") (pinfunction "1_1") (pintype "passive"))
      (node (ref "STM32F303VB") (pin "94") (pinfunction "BOOT0_94") (pintype "bidirectional"))
    )
    (net (code "9") (name "/BUTTON1") (class "Default")
      (node (ref "PCB2") (pin "P$47") (pinfunction "GPIO4_P$47") (pintype "bidirectional"))
      (node (ref "S1") (pin "2") (pinfunction "2_2") (pintype "bidirectional"))
      (node (ref "STM32F303VB") (pin "53") (pinfunction "PB14_53") (pintype "bidirectional"))
    )
    (net (code "11") (name "/CSESP_STM32") (class "Default")
      (node (ref "SJ19") (pin "1") (pinfunction "1_1") (pintype "passive"))
      (node (ref "U1") (pin "27") (pinfunction "IO16_27") (pintype "bidirectional"))
    )
    (net (code "12") (name "/CS_RFM69") (class "Default")
      (node (ref "PCB2") (pin "P$64") (pinfunction "GPIO8_P$64") (pintype "bidirectional"))
      (node (ref "RFM69HCW") (pin "14") (pinfunction "~{SEL}_14") (pintype "input"))
      (node (ref "SJ13") (pin "2") (pinfunction "2_2") (pintype "passive"))
    )
    (net (code "13") (name "/CS_STM32") (class "Default")
      (node (ref "SJ14") (pin "1") (pinfunction "1_1") (pintype "passive"))
      (node (ref "SJ19") (pin "2") (pinfunction "2_2") (pintype "passive"))
      (node (ref "SJ8") (pin "2") (pinfunction "2_2") (pintype "passive"))
    )
    (net (code "14") (name "/CT1") (class "Default")
      (node (ref "CF1") (pin "2") (pinfunction "2_2") (pintype "passive"))
      (node (ref "RF1") (pin "2") (pinfunction "2_2") (pintype "passive"))
      (node (ref "STM32F303VB") (pin "44") (pinfunction "PE13_44") (pintype "bidirectional"))
    )
    (net (code "15") (name "/CT1_EX") (class "Default")
      (node (ref "EXPANSION_MODULE") (pin "3") (pinfunction "3_3") (pintype "passive"))
      (node (ref "STM32F303VB") (pin "29") (pinfunction "PA4_29") (pintype "bidirectional"))
    )
    (net (code "16") (name "/CT2") (class "Default")
      (node (ref "CF2") (pin "2") (pinfunction "2_2") (pintype "passive"))
      (node (ref "RF2") (pin "2") (pinfunction "2_2") (pintype "passive"))
      (node (ref "STM32F303VB") (pin "43") (pinfunction "PE12_43") (pintype "bidirectional"))
    )
    (net (code "17") (name "/CT2_EX") (class "Default")
      (node (ref "EXPANSION_MODULE") (pin "6") (pinfunction "6_6") (pintype "passive"))
      (node (ref "STM32F303VB") (pin "30") (pinfunction "PA5_30") (pintype "bidirectional"))
    )
    (net (code "18") (name "/CT3") (class "Default")
      (node (ref "CF3") (pin "2") (pinfunction "2_2") (pintype "passive"))
      (node (ref "RF3") (pin "2") (pinfunction "2_2") (pintype "passive"))
      (node (ref "STM32F303VB") (pin "42") (pinfunction "PE11_42") (pintype "bidirectional"))
    )
    (net (code "19") (name "/CT3_EX") (class "Default")
      (node (ref "EXPANSION_MODULE") (pin "5") (pinfunction "5_5") (pintype "passive"))
      (node (ref "STM32F303VB") (pin "31") (pinfunction "PA6_31") (pintype "bidirectional"))
    )
    (net (code "20") (name "/CT4") (class "Default")
      (node (ref "CF4") (pin "2") (pinfunction "2_2") (pintype "passive"))
      (node (ref "RF4") (pin "2") (pinfunction "2_2") (pintype "passive"))
      (node (ref "STM32F303VB") (pin "41") (pinfunction "PE10_41") (pintype "bidirectional"))
    )
    (net (code "21") (name "/CT4_EX") (class "Default")
      (node (ref "EXPANSION_MODULE") (pin "8") (pinfunction "8_8") (pintype "passive"))
      (node (ref "STM32F303VB") (pin "32") (pinfunction "PA7_32") (pintype "bidirectional"))
    )
    (net (code "22") (name "/CT5") (class "Default")
      (node (ref "CF5") (pin "2") (pinfunction "2_2") (pintype "passive"))
      (node (ref "RF5") (pin "2") (pinfunction "2_2") (pintype "passive"))
      (node (ref "STM32F303VB") (pin "40") (pinfunction "PE9_40") (pintype "bidirectional"))
    )
    (net (code "23") (name "/CT5_EX") (class "Default")
      (node (ref "EXPANSION_MODULE") (pin "7") (pinfunction "7_7") (pintype "passive"))
      (node (ref "STM32F303VB") (pin "33") (pinfunction "PC4_33") (pintype "bidirectional"))
    )
    (net (code "24") (name "/CT6") (class "Default")
      (node (ref "CF6") (pin "2") (pinfunction "2_2") (pintype "passive"))
      (node (ref "RF6") (pin "2") (pinfunction "2_2") (pintype "passive"))
      (node (ref "STM32F303VB") (pin "39") (pinfunction "PE8_39") (pintype "bidirectional"))
    )
    (net (code "25") (name "/CT6_EX") (class "Default")
      (node (ref "EXPANSION_MODULE") (pin "10") (pinfunction "10_10") (pintype "passive"))
      (node (ref "STM32F303VB") (pin "15") (pinfunction "PC0_15") (pintype "bidirectional"))
    )
    (net (code "26") (name "/CT7") (class "Default")
      (node (ref "CF7") (pin "2") (pinfunction "2_2") (pintype "passive"))
      (node (ref "RF7") (pin "2") (pinfunction "2_2") (pintype "passive"))
      (node (ref "STM32F303VB") (pin "38") (pinfunction "PE7_38") (pintype "bidirectional"))
    )
    (net (code "27") (name "/CT7_EX") (class "Default")
      (node (ref "EXPANSION_MODULE") (pin "9") (pinfunction "9_9") (pintype "passive"))
      (node (ref "STM32F303VB") (pin "16") (pinfunction "PC1_16") (pintype "bidirectional"))
    )
    (net (code "28") (name "/CT8") (class "Default")
      (node (ref "CF8") (pin "2") (pinfunction "2_2") (pintype "passive"))
      (node (ref "RF8") (pin "2") (pinfunction "2_2") (pintype "passive"))
      (node (ref "STM32F303VB") (pin "36") (pinfunction "PB1_36") (pintype "bidirectional"))
    )
    (net (code "29") (name "/CT9") (class "Default")
      (node (ref "CF9") (pin "2") (pinfunction "2_2") (pintype "passive"))
      (node (ref "RF9") (pin "2") (pinfunction "2_2") (pintype "passive"))
      (node (ref "STM32F303VB") (pin "35") (pinfunction "PB0_35") (pintype "bidirectional"))
    )
    (net (code "30") (name "/D+") (class "Default")
      (node (ref "R6") (pin "2") (pinfunction "2_2") (pintype "passive"))
      (node (ref "STM32F303VB") (pin "71") (pinfunction "PA12_71") (pintype "bidirectional"))
      (node (ref "USB-C") (pin "A6") (pinfunction "D1+_A6") (pintype "passive"))
      (node (ref "USB-C") (pin "B6") (pinfunction "D2+_B6") (pintype "passive"))
    )
    (net (code "31") (name "/D-") (class "Default")
      (node (ref "STM32F303VB") (pin "70") (pinfunction "PA11_70") (pintype "bidirectional"))
      (node (ref "USB-C") (pin "A7") (pinfunction "D1-_A7") (pintype "passive"))
      (node (ref "USB-C") (pin "B7") (pinfunction "D2-_B7") (pintype "passive"))
    )
    (net (code "32") (name "/DIO0") (class "Default")
      (node (ref "PCB2") (pin "P$58") (pinfunction "GPIO24_P$58") (pintype "bidirectional"))
      (node (ref "RFM69HCW") (pin "2") (pinfunction "~{IRQ}_2") (pintype "output"))
      (node (ref "STM32F303VB") (pin "89") (pinfunction "PB3_89") (pintype "bidirectional"))
      (node (ref "U1") (pin "24") (pinfunction "IO2_24") (pintype "bidirectional"))
    )
    (net (code "33") (name "/DS18B20_2") (class "Default")
      (node (ref "3POLE_1") (pin "P$2") (pinfunction "2_P$2") (pintype "bidirectional"))
      (node (ref "D14") (pin "K") (pinfunction "C_K") (pintype "passive"))
      (node (ref "R8") (pin "1") (pinfunction "1_1") (pintype "passive"))
      (node (ref "STM32F303VB") (pin "61") (pinfunction "PD14_61") (pintype "bidirectional"))
    )
    (net (code "34") (name "/DS18B20_RJ45") (class "Default")
      (node (ref "R1") (pin "1") (pinfunction "1_1") (pintype "passive"))
      (node (ref "RJ45_1") (pin "4") (pinfunction "4_4") (pintype "bidirectional"))
      (node (ref "STM32F303VB") (pin "66") (pinfunction "PC9_66") (pintype "bidirectional"))
    )
    (net (code "35") (name "/HSE_IN") (class "Default")
      (node (ref "HSE") (pin "1") (pinfunction "1_1") (pintype "passive"))
      (node (ref "STM32F303VB") (pin "12") (pinfunction "PF0/OSC_IN_12") (pintype "bidirectional"))
    )
    (net (code "36") (name "/HSE_OUT") (class "Default")
      (node (ref "HSE") (pin "3") (pinfunction "2_3") (pintype "passive"))
      (node (ref "STM32F303VB") (pin "13") (pinfunction "PF1/OSC_OUT_13") (pintype "bidirectional"))
    )
    (net (code "37") (name "/HSPICS0") (class "Default")
      (node (ref "SJ13") (pin "1") (pinfunction "1_1") (pintype "passive"))
      (node (ref "U1") (pin "23") (pinfunction "IO15_23") (pintype "bidirectional"))
    )
    (net (code "38") (name "/HSPID") (class "Default")
      (node (ref "SJ9") (pin "1") (pinfunction "1_1") (pintype "passive"))
      (node (ref "U1") (pin "16") (pinfunction "IO13_16") (pintype "bidirectional"))
    )
    (net (code "39") (name "/HSPIQ") (class "Default")
      (node (ref "SJ4") (pin "1") (pinfunction "1_1") (pintype "passive"))
      (node (ref "U1") (pin "14") (pinfunction "IO12_14") (pintype "bidirectional"))
    )
    (net (code "40") (name "/HSPI_CLK") (class "Default")
      (node (ref "SJ10") (pin "1") (pinfunction "1_1") (pintype "passive"))
      (node (ref "U1") (pin "13") (pinfunction "IO14_13") (pintype "bidirectional"))
    )
    (net (code "41") (name "/IO1_EX") (class "Default")
      (node (ref "EXPANSION_MODULE") (pin "15") (pinfunction "15_15") (pintype "passive"))
      (node (ref "STM32F303VB") (pin "97") (pinfunction "PE0_97") (pintype "bidirectional"))
    )
    (net (code "42") (name "/IO2_EX") (class "Default")
      (node (ref "EXPANSION_MODULE") (pin "16") (pinfunction "16_16") (pintype "passive"))
      (node (ref "STM32F303VB") (pin "98") (pinfunction "PE1_98") (pintype "bidirectional"))
    )
    (net (code "43") (name "/IO3_EX") (class "Default")
      (node (ref "EXPANSION_MODULE") (pin "17") (pinfunction "17_17") (pintype "passive"))
      (node (ref "STM32F303VB") (pin "1") (pinfunction "PE2_1") (pintype "bidirectional"))
    )
    (net (code "44") (name "/IO4_EX") (class "Default")
      (node (ref "EXPANSION_MODULE") (pin "18") (pinfunction "18_18") (pintype "passive"))
      (node (ref "STM32F303VB") (pin "2") (pinfunction "PE3_2") (pintype "bidirectional"))
    )
    (net (code "45") (name "/IO5_EX") (class "Default")
      (node (ref "EXPANSION_MODULE") (pin "19") (pinfunction "19_19") (pintype "passive"))
      (node (ref "STM32F303VB") (pin "3") (pinfunction "PE4_3") (pintype "bidirectional"))
    )
    (net (code "46") (name "/IO6_EX") (class "Default")
      (node (ref "EXPANSION_MODULE") (pin "21") (pinfunction "21_21") (pintype "passive"))
      (node (ref "STM32F303VB") (pin "4") (pinfunction "PE5_4") (pintype "bidirectional"))
    )
    (net (code "47") (name "/IO7_EX") (class "Default")
      (node (ref "EXPANSION_MODULE") (pin "23") (pinfunction "23_23") (pintype "passive"))
      (node (ref "STM32F303VB") (pin "5") (pinfunction "PE6_5") (pintype "bidirectional"))
    )
    (net (code "48") (name "/IO8_EX") (class "Default")
      (node (ref "EXPANSION_MODULE") (pin "25") (pinfunction "25_25") (pintype "passive"))
      (node (ref "STM32F303VB") (pin "91") (pinfunction "PB5_91") (pintype "bidirectional"))
    )
    (net (code "49") (name "/IO11_EX") (class "Default")
      (node (ref "STM32F303VB") (pin "95") (pinfunction "PB8_95") (pintype "bidirectional"))
    )
    (net (code "50") (name "/LED1_GREEN") (class "Default")
      (node (ref "R3") (pin "2") (pinfunction "2_2") (pintype "passive"))
      (node (ref "STM32F303VB") (pin "55") (pinfunction "PD8_55") (pintype "bidirectional"))
    )
    (net (code "51") (name "/LED2_YELLOW") (class "Default")
      (node (ref "R4") (pin "2") (pinfunction "2_2") (pintype "passive"))
      (node (ref "STM32F303VB") (pin "56") (pinfunction "PD9_56") (pintype "bidirectional"))
    )
    (net (code "52") (name "/LED3_RED") (class "Default")
      (node (ref "R5") (pin "2") (pinfunction "2_2") (pintype "passive"))
      (node (ref "STM32F303VB") (pin "57") (pinfunction "PD10_57") (pintype "bidirectional"))
    )
    (net (code "53") (name "/MBUS_INPUT") (class "Default")
      (node (ref "3POLE_7") (pin "P$2") (pinfunction "2_P$2") (pintype "bidirectional"))
      (node (ref "Q1") (pin "2") (pinfunction "E_2") (pintype "passive"))
      (node (ref "R17") (pin "1") (pinfunction "1_1") (pintype "passive"))
    )
    (net (code "54") (name "/MBUS_RX") (class "Default")
      (node (ref "PCB2") (pin "P$56") (pinfunction "GPIO23_P$56") (pintype "bidirectional"))
      (node (ref "R18") (pin "2") (pinfunction "2_2") (pintype "passive"))
      (node (ref "SJ11") (pin "2") (pinfunction "2_2") (pintype "passive"))
    )
    (net (code "55") (name "/MBUS_TX") (class "Default")
      (node (ref "PCB2") (pin "P$52") (pinfunction "GPIO18_P$52") (pintype "bidirectional"))
      (node (ref "R19") (pin "2") (pinfunction "2_2") (pintype "passive"))
      (node (ref "SJ12") (pin "2") (pinfunction "2_2") (pintype "passive"))
    )
    (net (code "56") (name "/MISO") (class "Default")
      (node (ref "RFM69HCW") (pin "1") (pinfunction "SDO_1") (pintype "output"))
      (node (ref "SJ16") (pin "2") (pinfunction "2_2") (pintype "passive"))
      (node (ref "SJ4") (pin "2") (pinfunction "2_2") (pintype "passive"))
      (node (ref "SJ6") (pin "1") (pinfunction "1_1") (pintype "passive"))
    )
    (net (code "57") (name "/MOSI") (class "Default")
      (node (ref "RFM69HCW") (pin "12") (pinfunction "SDI_12") (pintype "input"))
      (node (ref "SJ17") (pin "2") (pinfunction "2_2") (pintype "passive"))
      (node (ref "SJ5") (pin "1") (pinfunction "1_1") (pintype "passive"))
      (node (ref "SJ9") (pin "2") (pinfunction "2_2") (pintype "passive"))
    )
    (net (code "58") (name "/N$21") (class "Default")
      (node (ref "R6") (pin "1") (pinfunction "1_1") (pintype "passive"))
      (node (ref "SJ22") (pin "2") (pinfunction "2_2") (pintype "passive"))
    )
    (net (code "59") (name "/NRST") (class "Default")
      (node (ref "JP3") (pin "6") (pinfunction "6_6") (pintype "passive"))
      (node (ref "PCB2") (pin "P$69") (pinfunction "GPIO5_P$69") (pintype "bidirectional"))
      (node (ref "RFM69HCW") (pin "6") (pinfunction "~{RES}_6") (pintype "bidirectional"))
      (node (ref "S2") (pin "2") (pinfunction "2_2") (pintype "bidirectional"))
      (node (ref "STM32F303VB") (pin "14") (pinfunction "NRST_14") (pintype "bidirectional"))
    )
    (net (code "60") (name "/PC14") (class "Default")
      (node (ref "LSE") (pin "P$1") (pinfunction "1_P$1") (pintype "passive"))
      (node (ref "STM32F303VB") (pin "8") (pinfunction "PC14/OSC32_IN_8") (pintype "bidirectional"))
    )
    (net (code "61") (name "/PC15") (class "Default")
      (node (ref "LSE") (pin "P$4") (pinfunction "2_P$4") (pintype "passive"))
      (node (ref "STM32F303VB") (pin "9") (pinfunction "PC15/OSC32_OUT_9") (pintype "bidirectional"))
    )
    (net (code "62") (name "/PULSE1_RJ45") (class "Default")
      (node (ref "C22") (pin "1") (pinfunction "1_1") (pintype "passive"))
      (node (ref "RJ45_1") (pin "6") (pinfunction "6_6") (pintype "bidirectional"))
      (node (ref "STM32F303VB") (pin "67") (pinfunction "PA8_67") (pintype "bidirectional"))
    )
    (net (code "63") (name "/PULSE2") (class "Default")
      (node (ref "3POLE_5") (pin "P$2") (pinfunction "2_P$2") (pintype "bidirectional"))
      (node (ref "C20") (pin "1") (pinfunction "1_1") (pintype "passive"))
      (node (ref "D18") (pin "K") (pinfunction "C_K") (pintype "passive"))
      (node (ref "STM32F303VB") (pin "65") (pinfunction "PC8_65") (pintype "bidirectional"))
    )
    (net (code "64") (name "/PUSHIN_1") (class "Default")
      (node (ref "3POLE_6") (pin "P$2") (pinfunction "2_P$2") (pintype "bidirectional"))
      (node (ref "C21") (pin "1") (pinfunction "1_1") (pintype "passive"))
      (node (ref "D19") (pin "K") (pinfunction "C_K") (pintype "passive"))
      (node (ref "STM32F303VB") (pin "96") (pinfunction "PB9_96") (pintype "bidirectional"))
    )
    (net (code "65") (name "/PUSHIN_2") (class "Default")
      (node (ref "3POLE_2") (pin "P$2") (pinfunction "2_P$2") (pintype "bidirectional"))
      (node (ref "C10") (pin "1") (pinfunction "1_1") (pintype "passive"))
      (node (ref "D15") (pin "K") (pinfunction "C_K") (pintype "passive"))
      (node (ref "STM32F303VB") (pin "62") (pinfunction "PD15_62") (pintype "bidirectional"))
    )
    (net (code "66") (name "/PUSHIN_3") (class "Default")
      (node (ref "3POLE_3") (pin "P$2") (pinfunction "2_P$2") (pintype "bidirectional"))
      (node (ref "C15") (pin "1") (pinfunction "1_1") (pintype "passive"))
      (node (ref "D16") (pin "K") (pinfunction "C_K") (pintype "passive"))
      (node (ref "STM32F303VB") (pin "63") (pinfunction "PC6_63") (pintype "bidirectional"))
    )
    (net (code "67") (name "/PUSHIN_4") (class "Default")
      (node (ref "3POLE_4") (pin "P$2") (pinfunction "2_P$2") (pintype "bidirectional"))
      (node (ref "C19") (pin "1") (pinfunction "1_1") (pintype "passive"))
      (node (ref "D17") (pin "K") (pinfunction "C_K") (pintype "passive"))
      (node (ref "STM32F303VB") (pin "64") (pinfunction "PC7_64") (pintype "bidirectional"))
    )
    (net (code "68") (name "/RPI_GPIO16") (class "Default")
      (node (ref "PCB2") (pin "P$76") (pinfunction "GPIO16_P$76") (pintype "bidirectional"))
      (node (ref "STM32F303VB") (pin "59") (pinfunction "PD12_59") (pintype "bidirectional"))
    )
    (net (code "69") (name "/RPI_GPIO20") (class "Default")
      (node (ref "PCB2") (pin "P$78") (pinfunction "GPIO20_P$78") (pintype "bidirectional"))
      (node (ref "STM32F303VB") (pin "60") (pinfunction "PD13_60") (pintype "bidirectional"))
    )
    (net (code "70") (name "/RPI_MISO") (class "Default")
      (node (ref "PCB2") (pin "P$61") (pinfunction "GPIO9_P$61") (pintype "bidirectional"))
      (node (ref "SJ6") (pin "2") (pinfunction "2_2") (pintype "passive"))
    )
    (net (code "71") (name "/RPI_MOSI") (class "Default")
      (node (ref "PCB2") (pin "P$59") (pinfunction "GPIO10_P$59") (pintype "bidirectional"))
      (node (ref "SJ5") (pin "2") (pinfunction "2_2") (pintype "passive"))
    )
    (net (code "72") (name "/RPI_SPI_CLK") (class "Default")
      (node (ref "PCB2") (pin "P$63") (pinfunction "GPIO11_P$63") (pintype "bidirectional"))
      (node (ref "SJ7") (pin "2") (pinfunction "2_2") (pintype "passive"))
    )
    (net (code "73") (name "/SCL") (class "Default")
      (node (ref "EXPANSION_MODULE") (pin "22") (pinfunction "22_22") (pintype "passive"))
      (node (ref "PCB2") (pin "P$68") (pinfunction "ID_SC*_P$68") (pintype "bidirectional"))
      (node (ref "STM32F303VB") (pin "92") (pinfunction "PB6_92") (pintype "bidirectional"))
      (node (ref "U1") (pin "36") (pinfunction "IO22_36") (pintype "bidirectional"))
    )
    (net (code "74") (name "/SDA") (class "Default")
      (node (ref "EXPANSION_MODULE") (pin "20") (pinfunction "20_20") (pintype "passive"))
      (node (ref "PCB2") (pin "P$67") (pinfunction "ID_SD*_P$67") (pintype "bidirectional"))
      (node (ref "STM32F303VB") (pin "93") (pinfunction "PB7_93") (pintype "bidirectional"))
      (node (ref "U1") (pin "33") (pinfunction "IO21_33") (pintype "bidirectional"))
    )
    (net (code "75") (name "/SPI3_CLK") (class "Default")
      (node (ref "SJ15") (pin "1") (pinfunction "1_1") (pintype "passive"))
      (node (ref "STM32F303VB") (pin "78") (pinfunction "PC10_78") (pintype "bidirectional"))
    )
    (net (code "76") (name "/SPI3_CS") (class "Default")
      (node (ref "SJ14") (pin "2") (pinfunction "2_2") (pintype "passive"))
      (node (ref "STM32F303VB") (pin "77") (pinfunction "PA15_77") (pintype "bidirectional"))
    )
    (net (code "77") (name "/SPI3_CS_ESP") (class "Default")
      (node (ref "STM32F303VB") (pin "84") (pinfunction "PD3_84") (pintype "bidirectional"))
    )
    (net (code "78") (name "/SPI3_MISO") (class "Default")
      (node (ref "SJ16") (pin "1") (pinfunction "1_1") (pintype "passive"))
      (node (ref "STM32F303VB") (pin "79") (pinfunction "PC11_79") (pintype "bidirectional"))
    )
    (net (code "79") (name "/SPI3_MOSI") (class "Default")
      (node (ref "SJ17") (pin "1") (pinfunction "1_1") (pintype "passive"))
      (node (ref "STM32F303VB") (pin "80") (pinfunction "PC12_80") (pintype "bidirectional"))
    )
    (net (code "80") (name "/SPI_CLK") (class "Default")
      (node (ref "RFM69HCW") (pin "13") (pinfunction "SCK_13") (pintype "input"))
      (node (ref "SJ10") (pin "2") (pinfunction "2_2") (pintype "passive"))
      (node (ref "SJ15") (pin "2") (pinfunction "2_2") (pintype "passive"))
      (node (ref "SJ7") (pin "1") (pinfunction "1_1") (pintype "passive"))
    )
    (net (code "81") (name "/SWCLK") (class "Default")
      (node (ref "JP3") (pin "7") (pinfunction "7_7") (pintype "passive"))
      (node (ref "STM32F303VB") (pin "76") (pinfunction "PA14_76") (pintype "bidirectional"))
    )
    (net (code "82") (name "/SWDIO") (class "Default")
      (node (ref "JP3") (pin "8") (pinfunction "8_8") (pintype "passive"))
      (node (ref "STM32F303VB") (pin "72") (pinfunction "PA13_72") (pintype "bidirectional"))
    )
    (net (code "83") (name "/UART1_RX") (class "Default")
      (node (ref "PCB2") (pin "P$48") (pinfunction "GPIO14_P$48") (pintype "bidirectional"))
      (node (ref "SJ11") (pin "1") (pinfunction "1_1") (pintype "passive"))
      (node (ref "SJ20") (pin "1") (pinfunction "1_1") (pintype "passive"))
    )
    (net (code "84") (name "/UART1_TX") (class "Default")
      (node (ref "PCB2") (pin "P$50") (pinfunction "GPIO15_P$50") (pintype "bidirectional"))
      (node (ref "SJ12") (pin "1") (pinfunction "1_1") (pintype "passive"))
      (node (ref "SJ21") (pin "1") (pinfunction "1_1") (pintype "passive"))
    )
    (net (code "85") (name "/UART2_RX") (class "Default")
      (node (ref "JP3") (pin "4") (pinfunction "4_4") (pintype "passive"))
      (node (ref "STM32F303VB") (pin "26") (pinfunction "PA3_26") (pintype "bidirectional"))
    )
    (net (code "86") (name "/UART2_TX") (class "Default")
      (node (ref "JP3") (pin "5") (pinfunction "5_5") (pintype "passive"))
      (node (ref "STM32F303VB") (pin "25") (pinfunction "PA2_25") (pintype "bidirectional"))
      (node (ref "STM32F303VB") (pin "86") (pinfunction "PD5_86") (pintype "bidirectional"))
    )
    (net (code "87") (name "/USART3_RX") (class "Default")
      (node (ref "SJ3") (pin "2") (pinfunction "2_2") (pintype "passive"))
      (node (ref "STM32F303VB") (pin "48") (pinfunction "PB11_48") (pintype "bidirectional"))
    )
    (net (code "88") (name "/USART3_TX") (class "Default")
      (node (ref "SJ18") (pin "2") (pinfunction "2_2") (pintype "passive"))
      (node (ref "STM32F303VB") (pin "47") (pinfunction "PB10_47") (pintype "bidirectional"))
    )
    (net (code "89") (name "/VBAT") (class "Default")
      (node (ref "C23") (pin "+") (pinfunction "+_+") (pintype "passive"))
      (node (ref "Q4") (pin "2") (pinfunction "S_2") (pintype "passive"))
      (node (ref "STM32F303VB") (pin "6") (pinfunction "VBAT_6") (pintype "bidirectional"))
    )
    (net (code "90") (name "/VSIG1") (class "Default")
      (node (ref "CFV1") (pin "2") (pinfunction "2_2") (pintype "passive"))
      (node (ref "D2") (pin "K") (pinfunction "C_K") (pintype "passive"))
      (node (ref "RFV1") (pin "2") (pinfunction "2_2") (pintype "passive"))
      (node (ref "STM32F303VB") (pin "23") (pinfunction "PA0_23") (pintype "bidirectional"))
    )
    (net (code "91") (name "/VSIG2") (class "Default")
      (node (ref "CFV2") (pin "2") (pinfunction "2_2") (pintype "passive"))
      (node (ref "D3") (pin "K") (pinfunction "C_K") (pintype "passive"))
      (node (ref "RFV2") (pin "2") (pinfunction "2_2") (pintype "passive"))
      (node (ref "STM32F303VB") (pin "24") (pinfunction "PA1_24") (pintype "bidirectional"))
    )
    (net (code "92") (name "/VSIG3") (class "Default")
      (node (ref "CFV3") (pin "2") (pinfunction "2_2") (pintype "passive"))
      (node (ref "D4") (pin "K") (pinfunction "C_K") (pintype "passive"))
      (node (ref "RFV3") (pin "2") (pinfunction "2_2") (pintype "passive"))
      (node (ref "STM32F303VB") (pin "27") (pinfunction "PF4_27") (pintype "bidirectional"))
    )
    (net (code "93") (name "/VSIG4") (class "Default")
      (node (ref "STM32F303VB") (pin "17") (pinfunction "PC2_17") (pintype "bidirectional"))
    )
    (net (code "94") (name "/VSIG5") (class "Default")
      (node (ref "STM32F303VB") (pin "18") (pinfunction "PC3_18") (pintype "bidirectional"))
    )
    (net (code "95") (name "/VSIG6") (class "Default")
      (node (ref "STM32F303VB") (pin "19") (pinfunction "PF2_19") (pintype "bidirectional"))
    )
    (net (code "96") (name "/VT1_EX") (class "Default")
      (node (ref "EXPANSION_MODULE") (pin "11") (pinfunction "11_11") (pintype "passive"))
    )
    (net (code "97") (name "/VT2_EX") (class "Default")
      (node (ref "EXPANSION_MODULE") (pin "12") (pinfunction "12_12") (pintype "passive"))
    )
    (net (code "98") (name "/VT3_EX") (class "Default")
      (node (ref "EXPANSION_MODULE") (pin "13") (pinfunction "13_13") (pintype "passive"))
    )
    (net (code "99") (name "GND") (class "Default")
      (node (ref "3POLE_1") (pin "P$3") (pinfunction "3_P$3") (pintype "bidirectional"))
      (node (ref "3POLE_2") (pin "P$3") (pinfunction "3_P$3") (pintype "bidirectional"))
      (node (ref "3POLE_3") (pin "P$3") (pinfunction "3_P$3") (pintype "bidirectional"))
      (node (ref "3POLE_4") (pin "P$3") (pinfunction "3_P$3") (pintype "bidirectional"))
      (node (ref "3POLE_5") (pin "P$3") (pinfunction "3_P$3") (pintype "bidirectional"))
      (node (ref "3POLE_6") (pin "P$3") (pinfunction "3_P$3") (pintype "bidirectional"))
      (node (ref "3POLE_7") (pin "P$1") (pinfunction "1_P$1") (pintype "bidirectional"))
      (node (ref "BOOT_ESP") (pin "1") (pinfunction "1_1") (pintype "passive"))
      (node (ref "C10") (pin "2") (pinfunction "2_2") (pintype "passive"))
      (node (ref "C11") (pin "2") (pinfunction "2_2") (pintype "passive"))
      (node (ref "C12") (pin "2") (pinfunction "2_2") (pintype "passive"))
      (node (ref "C13") (pin "2") (pinfunction "2_2") (pintype "passive"))
      (node (ref "C14") (pin "2") (pinfunction "2_2") (pintype "passive"))
      (node (ref "C15") (pin "2") (pinfunction "2_2") (pintype "passive"))
      (node (ref "C17") (pin "2") (pinfunction "2_2") (pintype "passive"))
      (node (ref "C18") (pin "2") (pinfunction "2_2") (pintype "passive"))
      (node (ref "C19") (pin "2") (pinfunction "2_2") (pintype "passive"))
      (node (ref "C2") (pin "2") (pinfunction "2_2") (pintype "passive"))
      (node (ref "C20") (pin "2") (pinfunction "2_2") (pintype "passive"))
      (node (ref "C21") (pin "2") (pinfunction "2_2") (pintype "passive"))
      (node (ref "C22") (pin "2") (pinfunction "2_2") (pintype "passive"))
      (node (ref "C23") (pin "-") (pinfunction "-_-") (pintype "passive"))
      (node (ref "C24") (pin "2") (pinfunction "2_2") (pintype "passive"))
      (node (ref "C25") (pin "2") (pinfunction "2_2") (pintype "passive"))
      (node (ref "C26") (pin "2") (pinfunction "2_2") (pintype "passive"))
      (node (ref "C27") (pin "2") (pinfunction "2_2") (pintype "passive"))
      (node (ref "C28") (pin "2") (pinfunction "2_2") (pintype "passive"))
      (node (ref "C29") (pin "2") (pinfunction "2_2") (pintype "passive"))
      (node (ref "C3") (pin "1") (pinfunction "1_1") (pintype "passive"))
      (node (ref "C30") (pin "2") (pinfunction "2_2") (pintype "passive"))
      (node (ref "C4") (pin "1") (pinfunction "1_1") (pintype "passive"))
      (node (ref "C5") (pin "1") (pinfunction "1_1") (pintype "passive"))
      (node (ref "C50*") (pin "1") (pinfunction "1_1") (pintype "passive"))
      (node (ref "C6") (pin "1") (pinfunction "1_1") (pintype "passive"))
      (node (ref "C7") (pin "2") (pinfunction "2_2") (pintype "passive"))
      (node (ref "C8") (pin "1") (pinfunction "1_1") (pintype "passive"))
      (node (ref "C9") (pin "1") (pinfunction "1_1") (pintype "passive"))
      (node (ref "CF1") (pin "1") (pinfunction "1_1") (pintype "passive"))
      (node (ref "CF2") (pin "1") (pinfunction "1_1") (pintype "passive"))
      (node (ref "CF3") (pin "1") (pinfunction "1_1") (pintype "passive"))
      (node (ref "CF4") (pin "1") (pinfunction "1_1") (pintype "passive"))
      (node (ref "CF5") (pin "1") (pinfunction "1_1") (pintype "passive"))
      (node (ref "CF6") (pin "1") (pinfunction "1_1") (pintype "passive"))
      (node (ref "CF7") (pin "1") (pinfunction "1_1") (pintype "passive"))
      (node (ref "CF8") (pin "1") (pinfunction "1_1") (pintype "passive"))
      (node (ref "CF9") (pin "1") (pinfunction "1_1") (pintype "passive"))
      (node (ref "CFV1") (pin "1") (pinfunction "1_1") (pintype "passive"))
      (node (ref "CFV2") (pin "1") (pinfunction "1_1") (pintype "passive"))
      (node (ref "CFV3") (pin "1") (pinfunction "1_1") (pintype "passive"))
      (node (ref "D1") (pin "A") (pinfunction "A_A") (pintype "passive"))
      (node (ref "D10") (pin "A") (pinfunction "A_A") (pintype "passive"))
      (node (ref "D11") (pin "A") (pinfunction "A_A") (pintype "passive"))
      (node (ref "D12") (pin "A") (pinfunction "A_A") (pintype "passive"))
      (node (ref "D13") (pin "A") (pinfunction "A_A") (pintype "passive"))
      (node (ref "D14") (pin "A") (pinfunction "A_A") (pintype "passive"))
      (node (ref "D15") (pin "A") (pinfunction "A_A") (pintype "passive"))
      (node (ref "D16") (pin "A") (pinfunction "A_A") (pintype "passive"))
      (node (ref "D17") (pin "A") (pinfunction "A_A") (pintype "passive"))
      (node (ref "D18") (pin "A") (pinfunction "A_A") (pintype "passive"))
      (node (ref "D19") (pin "A") (pinfunction "A_A") (pintype "passive"))
      (node (ref "D2") (pin "A") (pinfunction "A_A") (pintype "passive"))
      (node (ref "D22") (pin "A") (pinfunction "A_A") (pintype "passive"))
      (node (ref "D23") (pin "A") (pinfunction "A_A") (pintype "passive"))
      (node (ref "D25") (pin "A") (pinfunction "A_A") (pintype "passive"))
      (node (ref "D3") (pin "A") (pinfunction "A_A") (pintype "passive"))
      (node (ref "D4") (pin "A") (pinfunction "A_A") (pintype "passive"))
      (node (ref "D41*") (pin "A") (pinfunction "A_A") (pintype "passive"))
      (node (ref "D5") (pin "A") (pinfunction "A_A") (pintype "passive"))
      (node (ref "D6") (pin "A") (pinfunction "A_A") (pintype "passive"))
      (node (ref "D7") (pin "A") (pinfunction "A_A") (pintype "passive"))
      (node (ref "D8") (pin "A") (pinfunction "A_A") (pintype "passive"))
      (node (ref "D9") (pin "A") (pinfunction "A_A") (pintype "passive"))
      (node (ref "EXPANSION_MODULE") (pin "1") (pinfunction "1_1") (pintype "passive"))
      (node (ref "EXPANSION_MODULE") (pin "14") (pinfunction "14_14") (pintype "passive"))
      (node (ref "EXPANSION_MODULE") (pin "26") (pinfunction "26_26") (pintype "passive"))
      (node (ref "J$1") (pin "GND@0") (pinfunction "GND_GND@0") (pintype "bidirectional"))
      (node (ref "J$1") (pin "GND@1") (pinfunction "GND_GND@1") (pintype "bidirectional"))
      (node (ref "J$1") (pin "GND@2") (pinfunction "GND_GND@2") (pintype "bidirectional"))
      (node (ref "J$1") (pin "GND@3") (pinfunction "GND_GND@3") (pintype "bidirectional"))
      (node (ref "JP1") (pin "1") (pinfunction "1_1") (pintype "passive"))
      (node (ref "JP3") (pin "1") (pinfunction "1_1") (pintype "passive"))
      (node (ref "LED1") (pin "C") (pinfunction "C_C") (pintype "passive"))
      (node (ref "LED2") (pin "C") (pinfunction "C_C") (pintype "passive"))
      (node (ref "LED3") (pin "C") (pinfunction "C_C") (pintype "passive"))
      (node (ref "LED4") (pin "C") (pinfunction "C_C") (pintype "passive"))
      (node (ref "MCP1825") (pin "2") (pinfunction "GND_2") (pintype "power_in"))
      (node (ref "MCP1825") (pin "4") (pinfunction "GND_4") (pintype "power_in"))
      (node (ref "PCB2") (pin "P$46") (pinfunction "GND_P$46") (pintype "bidirectional"))
      (node (ref "PCB2") (pin "P$49") (pinfunction "GND_P$49") (pintype "bidirectional"))
      (node (ref "PCB2") (pin "P$54") (pinfunction "GND_P$54") (pintype "bidirectional"))
      (node (ref "PCB2") (pin "P$60") (pinfunction "GND_P$60") (pintype "bidirectional"))
      (node (ref "PCB2") (pin "P$65") (pinfunction "GND_P$65") (pintype "bidirectional"))
      (node (ref "PCB2") (pin "P$70") (pinfunction "GND_P$70") (pintype "bidirectional"))
      (node (ref "PCB2") (pin "P$74") (pinfunction "GND_P$74") (pintype "bidirectional"))
      (node (ref "PCB2") (pin "P$79") (pinfunction "GND_P$79") (pintype "bidirectional"))
      (node (ref "Q2") (pin "2") (pinfunction "E_2") (pintype "passive"))
      (node (ref "Q3") (pin "2") (pinfunction "E_2") (pintype "passive"))
      (node (ref "Q4") (pin "1") (pinfunction "G_1") (pintype "passive"))
      (node (ref "R14") (pin "1") (pinfunction "1_1") (pintype "passive"))
      (node (ref "R15") (pin "1") (pinfunction "1_1") (pintype "passive"))
      (node (ref "R16") (pin "1") (pinfunction "1_1") (pintype "passive"))
      (node (ref "R2") (pin "2") (pinfunction "2_2") (pintype "passive"))
      (node (ref "R23") (pin "1") (pinfunction "1_1") (pintype "passive"))
      (node (ref "RFM69HCW") (pin "10") (pinfunction "GND_10") (pintype "passive"))
      (node (ref "RFM69HCW") (pin "7") (pinfunction "GND_7") (pintype "passive"))
      (node (ref "RJ45_1") (pin "1") (pinfunction "1_1") (pintype "bidirectional"))
      (node (ref "RJ45_1") (pin "3") (pinfunction "3_3") (pintype "bidirectional"))
      (node (ref "RJ45_1") (pin "5") (pinfunction "5_5") (pintype "bidirectional"))
      (node (ref "S1") (pin "1") (pinfunction "1_1") (pintype "bidirectional"))
      (node (ref "S2") (pin "1") (pinfunction "1_1") (pintype "bidirectional"))
      (node (ref "STM32F303VB") (pin "20") (pinfunction "VSSA/VREF-_20") (pintype "bidirectional"))
      (node (ref "STM32F303VB") (pin "49") (pinfunction "VSS_49") (pintype "bidirectional"))
      (node (ref "STM32F303VB") (pin "74") (pinfunction "VSS_74") (pintype "bidirectional"))
      (node (ref "STM32F303VB") (pin "99") (pinfunction "VSS_99") (pintype "bidirectional"))
      (node (ref "U$2") (pin "P$1") (pinfunction "GND_P$1") (pintype "bidirectional"))
      (node (ref "U$2") (pin "P$2") (pinfunction "GND._P$2") (pintype "bidirectional"))
      (node (ref "U1") (pin "1") (pinfunction "GND_1") (pintype "power_in"))
      (node (ref "U1") (pin "15") (pinfunction "GND_15") (pintype "power_in"))
      (node (ref "U1") (pin "38") (pinfunction "GND_38") (pintype "power_in"))
      (node (ref "U1") (pin "39") (pinfunction "GND_39") (pintype "power_in"))
      (node (ref "USB-C") (pin "A1") (pinfunction "GND1_A1") (pintype "passive"))
      (node (ref "USB-C") (pin "A12") (pinfunction "GND2_A12") (pintype "passive"))
      (node (ref "USB-C") (pin "B1") (pinfunction "GND3_B1") (pintype "passive"))
      (node (ref "USB-C") (pin "B12") (pinfunction "GND4_B12") (pintype "passive"))
      (node (ref "USB-C") (pin "S1") (pinfunction "SHIELD_S1") (pintype "passive"))
      (node (ref "USB-C") (pin "S2") (pinfunction "SHIELD_S2") (pintype "passive"))
      (node (ref "USB-C") (pin "S3") (pinfunction "SHIELD_S3") (pintype "passive"))
      (node (ref "USB-C") (pin "S4") (pinfunction "SHIELD_S4") (pintype "passive"))
      (node (ref "VREF_3V3") (pin "2") (pinfunction "GND_2") (pintype "bidirectional"))
      (node (ref "VREF_3V3") (pin "3") (pinfunction "GND_3") (pintype "bidirectional"))
      (node (ref "VREF_3V3") (pin "5") (pinfunction "GND_5") (pintype "bidirectional"))
    )
    (net (code "100") (name "Net-(C16-Pad1)") (class "Default")
      (node (ref "C16") (pin "1") (pinfunction "1_1") (pintype "passive"))
      (node (ref "JP1") (pin "6") (pinfunction "6_6") (pintype "passive"))
    )
    (net (code "101") (name "Net-(CT1-2)") (class "Default")
      (node (ref "CT1") (pin "P$2") (pinfunction "2_P$2") (pintype "bidirectional"))
      (node (ref "D13") (pin "K") (pinfunction "C_K") (pintype "passive"))
      (node (ref "RB18") (pin "1") (pinfunction "1_1") (pintype "passive"))
      (node (ref "RB9") (pin "1") (pinfunction "1_1") (pintype "passive"))
      (node (ref "RF9") (pin "1") (pinfunction "1_1") (pintype "passive"))
    )
    (net (code "102") (name "Net-(CT2-2)") (class "Default")
      (node (ref "CT2") (pin "P$2") (pinfunction "2_P$2") (pintype "bidirectional"))
      (node (ref "D12") (pin "K") (pinfunction "C_K") (pintype "passive"))
      (node (ref "RB17") (pin "1") (pinfunction "1_1") (pintype "passive"))
      (node (ref "RB8") (pin "1") (pinfunction "1_1") (pintype "passive"))
      (node (ref "RF8") (pin "1") (pinfunction "1_1") (pintype "passive"))
    )
    (net (code "103") (name "Net-(CT3-2)") (class "Default")
      (node (ref "CT3") (pin "P$2") (pinfunction "2_P$2") (pintype "bidirectional"))
      (node (ref "D11") (pin "K") (pinfunction "C_K") (pintype "passive"))
      (node (ref "RB16") (pin "1") (pinfunction "1_1") (pintype "passive"))
      (node (ref "RB7") (pin "1") (pinfunction "1_1") (pintype "passive"))
      (node (ref "RF7") (pin "1") (pinfunction "1_1") (pintype "passive"))
    )
    (net (code "104") (name "Net-(CT4-2)") (class "Default")
      (node (ref "CT4") (pin "P$2") (pinfunction "2_P$2") (pintype "bidirectional"))
      (node (ref "D10") (pin "K") (pinfunction "C_K") (pintype "passive"))
      (node (ref "RB13") (pin "1") (pinfunction "1_1") (pintype "passive"))
      (node (ref "RB6") (pin "1") (pinfunction "1_1") (pintype "passive"))
      (node (ref "RF6") (pin "1") (pinfunction "1_1") (pintype "passive"))
    )
    (net (code "105") (name "Net-(CT5-2)") (class "Default")
      (node (ref "CT5") (pin "P$2") (pinfunction "2_P$2") (pintype "bidirectional"))
      (node (ref "D9") (pin "K") (pinfunction "C_K") (pintype "passive"))
      (node (ref "RB14") (pin "1") (pinfunction "1_1") (pintype "passive"))
      (node (ref "RB5") (pin "1") (pinfunction "1_1") (pintype "passive"))
      (node (ref "RF5") (pin "1") (pinfunction "1_1") (pintype "passive"))
    )
    (net (code "106") (name "Net-(CT6-2)") (class "Default")
      (node (ref "CT6") (pin "P$2") (pinfunction "2_P$2") (pintype "bidirectional"))
      (node (ref "D8") (pin "K") (pinfunction "C_K") (pintype "passive"))
      (node (ref "RB15") (pin "1") (pinfunction "1_1") (pintype "passive"))
      (node (ref "RB4") (pin "1") (pinfunction "1_1") (pintype "passive"))
      (node (ref "RF4") (pin "1") (pinfunction "1_1") (pintype "passive"))
    )
    (net (code "107") (name "Net-(CT7-2)") (class "Default")
      (node (ref "CT7") (pin "P$2") (pinfunction "2_P$2") (pintype "bidirectional"))
      (node (ref "D7") (pin "K") (pinfunction "C_K") (pintype "passive"))
      (node (ref "RB12") (pin "1") (pinfunction "1_1") (pintype "passive"))
      (node (ref "RB3") (pin "1") (pinfunction "1_1") (pintype "passive"))
      (node (ref "RF3") (pin "1") (pinfunction "1_1") (pintype "passive"))
    )
    (net (code "108") (name "Net-(CT8-2)") (class "Default")
      (node (ref "CT8") (pin "P$2") (pinfunction "2_P$2") (pintype "bidirectional"))
      (node (ref "D6") (pin "K") (pinfunction "C_K") (pintype "passive"))
      (node (ref "RB11") (pin "1") (pinfunction "1_1") (pintype "passive"))
      (node (ref "RB2") (pin "1") (pinfunction "1_1") (pintype "passive"))
      (node (ref "RF2") (pin "1") (pinfunction "1_1") (pintype "passive"))
    )
    (net (code "109") (name "Net-(CT9-2)") (class "Default")
      (node (ref "CT9") (pin "P$2") (pinfunction "2_P$2") (pintype "bidirectional"))
      (node (ref "D5") (pin "K") (pinfunction "C_K") (pintype "passive"))
      (node (ref "RB1") (pin "1") (pinfunction "1_1") (pintype "passive"))
      (node (ref "RB10") (pin "1") (pinfunction "1_1") (pintype "passive"))
      (node (ref "RF1") (pin "1") (pinfunction "1_1") (pintype "passive"))
    )
    (net (code "110") (name "Net-(D25-C)") (class "Default")
      (node (ref "D24") (pin "A") (pinfunction "A_A") (pintype "passive"))
      (node (ref "D25") (pin "K") (pinfunction "C_K") (pintype "passive"))
    )
    (net (code "111") (name "Net-(D41*-C)") (class "Default")
      (node (ref "D40*") (pin "A") (pinfunction "A_A") (pintype "passive"))
      (node (ref "D41*") (pin "K") (pinfunction "C_K") (pintype "passive"))
    )
    (net (code "112") (name "Net-(J$1-SIGNAL)") (class "Default")
      (node (ref "J$1") (pin "SIG") (pinfunction "SIGNAL_SIG") (pintype "bidirectional"))
      (node (ref "RFM69HCW") (pin "8") (pinfunction "ANT_8") (pintype "bidirectional"))
    )
    (net (code "113") (name "Net-(JP3-Pad2)") (class "Default")
      (node (ref "JP3") (pin "2") (pinfunction "2_2") (pintype "passive"))
      (node (ref "SJ1") (pin "1") (pinfunction "1_1") (pintype "passive"))
    )
    (net (code "114") (name "Net-(LED1-PadA)") (class "Default")
      (node (ref "LED1") (pin "A") (pinfunction "A_A") (pintype "passive"))
      (node (ref "R3") (pin "1") (pinfunction "1_1") (pintype "passive"))
    )
    (net (code "115") (name "Net-(LED2-PadA)") (class "Default")
      (node (ref "LED2") (pin "A") (pinfunction "A_A") (pintype "passive"))
      (node (ref "R4") (pin "1") (pinfunction "1_1") (pintype "passive"))
    )
    (net (code "116") (name "Net-(LED3-PadA)") (class "Default")
      (node (ref "LED3") (pin "A") (pinfunction "A_A") (pintype "passive"))
      (node (ref "R5") (pin "1") (pinfunction "1_1") (pintype "passive"))
    )
    (net (code "117") (name "Net-(LED4-PadA)") (class "Default")
      (node (ref "LED4") (pin "A") (pinfunction "A_A") (pintype "passive"))
      (node (ref "R10") (pin "1") (pinfunction "1_1") (pintype "passive"))
    )
    (net (code "118") (name "Net-(PCB2-GPIO12)") (class "Default")
      (node (ref "PCB2") (pin "P$72") (pinfunction "GPIO12_P$72") (pintype "bidirectional"))
      (node (ref "SJ8") (pin "1") (pinfunction "1_1") (pintype "passive"))
    )
    (net (code "119") (name "Net-(Q1-B)") (class "Default")
      (node (ref "Q1") (pin "1") (pinfunction "B_1") (pintype "passive"))
      (node (ref "Q3") (pin "3") (pinfunction "C_3") (pintype "passive"))
      (node (ref "R14") (pin "2") (pinfunction "2_2") (pintype "passive"))
      (node (ref "R9") (pin "1") (pinfunction "1_1") (pintype "passive"))
    )
    (net (code "120") (name "Net-(Q1-C)") (class "Default")
      (node (ref "Q1") (pin "3") (pinfunction "C_3") (pintype "passive"))
      (node (ref "Q2") (pin "1") (pinfunction "B_1") (pintype "passive"))
      (node (ref "R16") (pin "2") (pinfunction "2_2") (pintype "passive"))
    )
    (net (code "121") (name "Net-(Q2-C)") (class "Default")
      (node (ref "Q2") (pin "3") (pinfunction "C_3") (pintype "passive"))
      (node (ref "R11") (pin "1") (pinfunction "1_1") (pintype "passive"))
      (node (ref "R15") (pin "2") (pinfunction "2_2") (pintype "passive"))
      (node (ref "R19") (pin "1") (pinfunction "1_1") (pintype "passive"))
    )
    (net (code "122") (name "Net-(Q3-B)") (class "Default")
      (node (ref "Q3") (pin "1") (pinfunction "B_1") (pintype "passive"))
      (node (ref "R18") (pin "1") (pinfunction "1_1") (pintype "passive"))
    )
    (net (code "123") (name "Net-(RB16-Pad2)") (class "Default")
      (node (ref "RB16") (pin "2") (pinfunction "2_2") (pintype "passive"))
      (node (ref "RB7") (pin "2") (pinfunction "2_2") (pintype "passive"))
      (node (ref "S33") (pin "1") (pinfunction "1_1") (pintype "passive"))
    )
    (net (code "124") (name "Net-(RB17-Pad2)") (class "Default")
      (node (ref "RB17") (pin "2") (pinfunction "2_2") (pintype "passive"))
      (node (ref "RB8") (pin "2") (pinfunction "2_2") (pintype "passive"))
      (node (ref "S22") (pin "1") (pinfunction "1_1") (pintype "passive"))
    )
    (net (code "125") (name "Net-(RB18-Pad2)") (class "Default")
      (node (ref "RB18") (pin "2") (pinfunction "2_2") (pintype "passive"))
      (node (ref "RB9") (pin "2") (pinfunction "2_2") (pintype "passive"))
      (node (ref "S11") (pin "1") (pinfunction "1_1") (pintype "passive"))
    )
    (net (code "126") (name "Net-(RFV1-Pad1)") (class "Default")
      (node (ref "RFV1") (pin "1") (pinfunction "1_1") (pintype "passive"))
      (node (ref "RVPU1") (pin "1") (pinfunction "1_1") (pintype "passive"))
      (node (ref "RVPU11") (pin "1") (pinfunction "1_1") (pintype "passive"))
    )
    (net (code "127") (name "Net-(RFV2-Pad1)") (class "Default")
      (node (ref "RFV2") (pin "1") (pinfunction "1_1") (pintype "passive"))
      (node (ref "RVPU2") (pin "1") (pinfunction "1_1") (pintype "passive"))
      (node (ref "RVPU22") (pin "1") (pinfunction "1_1") (pintype "passive"))
    )
    (net (code "128") (name "Net-(RFV3-Pad1)") (class "Default")
      (node (ref "RFV3") (pin "1") (pinfunction "1_1") (pintype "passive"))
      (node (ref "RVPU3") (pin "2") (pinfunction "2_2") (pintype "passive"))
      (node (ref "RVPU33") (pin "1") (pinfunction "1_1") (pintype "passive"))
    )
    (net (code "129") (name "Net-(STM32F303VB-PA9)") (class "Default")
      (node (ref "STM32F303VB") (pin "68") (pinfunction "PA9_68") (pintype "bidirectional"))
      (node (ref "UART1") (pin "2") (pinfunction "2_2") (pintype "passive"))
    )
    (net (code "130") (name "Net-(STM32F303VB-PA10)") (class "Default")
      (node (ref "STM32F303VB") (pin "69") (pinfunction "PA10_69") (pintype "bidirectional"))
      (node (ref "UART1") (pin "1") (pinfunction "1_1") (pintype "passive"))
    )
    (net (code "131") (name "Net-(U1-EN)") (class "Default")
      (node (ref "C16") (pin "2") (pinfunction "2_2") (pintype "passive"))
      (node (ref "U1") (pin "3") (pinfunction "EN_3") (pintype "input"))
    )
    (net (code "132") (name "Net-(U1-IO0)") (class "Default")
      (node (ref "BOOT_ESP") (pin "2") (pinfunction "2_2") (pintype "passive"))
      (node (ref "U1") (pin "25") (pinfunction "IO0_25") (pintype "bidirectional"))
    )
    (net (code "133") (name "Net-(U1-RXD0)") (class "Default")
      (node (ref "JP1") (pin "4") (pinfunction "4_4") (pintype "passive"))
      (node (ref "SJ18") (pin "1") (pinfunction "1_1") (pintype "passive"))
      (node (ref "SJ21") (pin "2") (pinfunction "2_2") (pintype "passive"))
      (node (ref "U1") (pin "34") (pinfunction "RXD0_34") (pintype "bidirectional"))
    )
    (net (code "134") (name "Net-(U1-TXD0)") (class "Default")
      (node (ref "JP1") (pin "5") (pinfunction "5_5") (pintype "passive"))
      (node (ref "SJ20") (pin "2") (pinfunction "2_2") (pintype "passive"))
      (node (ref "SJ3") (pin "1") (pinfunction "1_1") (pintype "passive"))
      (node (ref "U1") (pin "35") (pinfunction "TXD0_35") (pintype "bidirectional"))
    )
    (net (code "135") (name "Net-(VT1-TIP)") (class "Default")
      (node (ref "RVPU1") (pin "2") (pinfunction "2_2") (pintype "passive"))
      (node (ref "VT1") (pin "PWR2") (pinfunction "TIP_PWR2") (pintype "bidirectional"))
    )
    (net (code "136") (name "Net-(VT2-TIP)") (class "Default")
      (node (ref "RVPU2") (pin "2") (pinfunction "2_2") (pintype "passive"))
      (node (ref "VT2") (pin "PWR2") (pinfunction "TIP_PWR2") (pintype "bidirectional"))
    )
    (net (code "137") (name "Net-(VT3-TIP)") (class "Default")
      (node (ref "RVPU3") (pin "1") (pinfunction "1_1") (pintype "passive"))
      (node (ref "VT3") (pin "PWR2") (pinfunction "TIP_PWR2") (pintype "bidirectional"))
    )
    (net (code "138") (name "unconnected-(CT1-3-PadP$3)") (class "Default")
      (node (ref "CT1") (pin "P$3") (pinfunction "3_P$3") (pintype "bidirectional"))
    )
    (net (code "139") (name "unconnected-(CT2-3-PadP$3)") (class "Default")
      (node (ref "CT2") (pin "P$3") (pinfunction "3_P$3") (pintype "bidirectional"))
    )
    (net (code "140") (name "unconnected-(CT3-3-PadP$3)") (class "Default")
      (node (ref "CT3") (pin "P$3") (pinfunction "3_P$3") (pintype "bidirectional"))
    )
    (net (code "141") (name "unconnected-(CT4-3-PadP$3)") (class "Default")
      (node (ref "CT4") (pin "P$3") (pinfunction "3_P$3") (pintype "bidirectional"))
    )
    (net (code "142") (name "unconnected-(CT5-3-PadP$3)") (class "Default")
      (node (ref "CT5") (pin "P$3") (pinfunction "3_P$3") (pintype "bidirectional"))
    )
    (net (code "143") (name "unconnected-(CT6-3-PadP$3)") (class "Default")
      (node (ref "CT6") (pin "P$3") (pinfunction "3_P$3") (pintype "bidirectional"))
    )
    (net (code "144") (name "unconnected-(CT7-3-PadP$3)") (class "Default")
      (node (ref "CT7") (pin "P$3") (pinfunction "3_P$3") (pintype "bidirectional"))
    )
    (net (code "145") (name "unconnected-(CT8-3-PadP$3)") (class "Default")
      (node (ref "CT8") (pin "P$3") (pinfunction "3_P$3") (pintype "bidirectional"))
    )
    (net (code "146") (name "unconnected-(CT9-3-PadP$3)") (class "Default")
      (node (ref "CT9") (pin "P$3") (pinfunction "3_P$3") (pintype "bidirectional"))
    )
    (net (code "147") (name "unconnected-(PCB2-3V3-PadP$41)") (class "Default")
      (node (ref "PCB2") (pin "P$41") (pinfunction "3V3_P$41") (pintype "bidirectional"))
    )
    (net (code "148") (name "unconnected-(PCB2-3V3-PadP$57)") (class "Default")
      (node (ref "PCB2") (pin "P$57") (pinfunction "3V3_P$57") (pintype "bidirectional"))
    )
    (net (code "149") (name "unconnected-(PCB2-GPIO2-PadP$43)") (class "Default")
      (node (ref "PCB2") (pin "P$43") (pinfunction "GPIO2_P$43") (pintype "bidirectional"))
    )
    (net (code "150") (name "unconnected-(PCB2-GPIO3-PadP$45)") (class "Default")
      (node (ref "PCB2") (pin "P$45") (pinfunction "GPIO3_P$45") (pintype "bidirectional"))
    )
    (net (code "151") (name "unconnected-(PCB2-GPIO6-PadP$71)") (class "Default")
      (node (ref "PCB2") (pin "P$71") (pinfunction "GPIO6_P$71") (pintype "bidirectional"))
    )
    (net (code "152") (name "unconnected-(PCB2-GPIO7-PadP$66)") (class "Default")
      (node (ref "PCB2") (pin "P$66") (pinfunction "GPIO7_P$66") (pintype "bidirectional"))
    )
    (net (code "153") (name "unconnected-(PCB2-GPIO13-PadP$73)") (class "Default")
      (node (ref "PCB2") (pin "P$73") (pinfunction "GPIO13_P$73") (pintype "bidirectional"))
    )
    (net (code "154") (name "unconnected-(PCB2-GPIO17-PadP$51)") (class "Default")
      (node (ref "PCB2") (pin "P$51") (pinfunction "GPIO17_P$51") (pintype "bidirectional"))
    )
    (net (code "155") (name "unconnected-(PCB2-GPIO19-PadP$75)") (class "Default")
      (node (ref "PCB2") (pin "P$75") (pinfunction "GPIO19_P$75") (pintype "bidirectional"))
    )
    (net (code "156") (name "unconnected-(PCB2-GPIO21-PadP$80)") (class "Default")
      (node (ref "PCB2") (pin "P$80") (pinfunction "GPIO21_P$80") (pintype "bidirectional"))
    )
    (net (code "157") (name "unconnected-(PCB2-GPIO22-PadP$55)") (class "Default")
      (node (ref "PCB2") (pin "P$55") (pinfunction "GPIO22_P$55") (pintype "bidirectional"))
    )
    (net (code "158") (name "unconnected-(PCB2-GPIO25-PadP$62)") (class "Default")
      (node (ref "PCB2") (pin "P$62") (pinfunction "GPIO25_P$62") (pintype "bidirectional"))
    )
    (net (code "159") (name "unconnected-(PCB2-GPIO26-PadP$77)") (class "Default")
      (node (ref "PCB2") (pin "P$77") (pinfunction "GPIO26_P$77") (pintype "bidirectional"))
    )
    (net (code "160") (name "unconnected-(PCB2-GPIO27-PadP$53)") (class "Default")
      (node (ref "PCB2") (pin "P$53") (pinfunction "GPIO27_P$53") (pintype "bidirectional"))
    )
    (net (code "161") (name "unconnected-(RFM69HCW-CLK-Pad5)") (class "Default")
      (node (ref "RFM69HCW") (pin "5") (pinfunction "CLK_5") (pintype "output"))
    )
    (net (code "162") (name "unconnected-(RFM69HCW-DCLK{slash}CFIL{slash}FFIT-Pad4)") (class "Default")
      (node (ref "RFM69HCW") (pin "4") (pinfunction "DCLK/CFIL/FFIT_4") (pintype "bidirectional"))
    )
    (net (code "163") (name "unconnected-(RFM69HCW-FSK{slash}DATA{slash}NFFS-Pad3)") (class "Default")
      (node (ref "RFM69HCW") (pin "3") (pinfunction "FSK/DATA/NFFS_3") (pintype "bidirectional"))
    )
    (net (code "164") (name "unconnected-(RFM69HCW-~{INT}-Pad11)") (class "Default")
      (node (ref "RFM69HCW") (pin "11") (pinfunction "~{INT}_11") (pintype "bidirectional"))
    )
    (net (code "165") (name "unconnected-(STM32F303VB-PB2-Pad37)") (class "Default")
      (node (ref "STM32F303VB") (pin "37") (pinfunction "PB2_37") (pintype "bidirectional"))
    )
    (net (code "166") (name "unconnected-(STM32F303VB-PB4-Pad90)") (class "Default")
      (node (ref "STM32F303VB") (pin "90") (pinfunction "PB4_90") (pintype "bidirectional"))
    )
    (net (code "167") (name "unconnected-(STM32F303VB-PB13-Pad52)") (class "Default")
      (node (ref "STM32F303VB") (pin "52") (pinfunction "PB13_52") (pintype "bidirectional"))
    )
    (net (code "168") (name "unconnected-(STM32F303VB-PC5-Pad34)") (class "Default")
      (node (ref "STM32F303VB") (pin "34") (pinfunction "PC5_34") (pintype "bidirectional"))
    )
    (net (code "169") (name "unconnected-(STM32F303VB-PC13-Pad7)") (class "Default")
      (node (ref "STM32F303VB") (pin "7") (pinfunction "PC13_7") (pintype "bidirectional"))
    )
    (net (code "170") (name "unconnected-(STM32F303VB-PD0-Pad81)") (class "Default")
      (node (ref "STM32F303VB") (pin "81") (pinfunction "PD0_81") (pintype "bidirectional"))
    )
    (net (code "171") (name "unconnected-(STM32F303VB-PD1-Pad82)") (class "Default")
      (node (ref "STM32F303VB") (pin "82") (pinfunction "PD1_82") (pintype "bidirectional"))
    )
    (net (code "172") (name "unconnected-(STM32F303VB-PD2-Pad83)") (class "Default")
      (node (ref "STM32F303VB") (pin "83") (pinfunction "PD2_83") (pintype "bidirectional"))
    )
    (net (code "173") (name "unconnected-(STM32F303VB-PD4-Pad85)") (class "Default")
      (node (ref "STM32F303VB") (pin "85") (pinfunction "PD4_85") (pintype "bidirectional"))
    )
    (net (code "174") (name "unconnected-(STM32F303VB-PD6-Pad87)") (class "Default")
      (node (ref "STM32F303VB") (pin "87") (pinfunction "PD6_87") (pintype "bidirectional"))
    )
    (net (code "175") (name "unconnected-(STM32F303VB-PD7-Pad88)") (class "Default")
      (node (ref "STM32F303VB") (pin "88") (pinfunction "PD7_88") (pintype "bidirectional"))
    )
    (net (code "176") (name "unconnected-(STM32F303VB-PE14-Pad45)") (class "Default")
      (node (ref "STM32F303VB") (pin "45") (pinfunction "PE14_45") (pintype "bidirectional"))
    )
    (net (code "177") (name "unconnected-(STM32F303VB-PE15-Pad46)") (class "Default")
      (node (ref "STM32F303VB") (pin "46") (pinfunction "PE15_46") (pintype "bidirectional"))
    )
    (net (code "178") (name "unconnected-(STM32F303VB-PF6-Pad73)") (class "Default")
      (node (ref "STM32F303VB") (pin "73") (pinfunction "PF6_73") (pintype "bidirectional"))
    )
    (net (code "179") (name "unconnected-(STM32F303VB-PF9-Pad10)") (class "Default")
      (node (ref "STM32F303VB") (pin "10") (pinfunction "PF9_10") (pintype "bidirectional"))
    )
    (net (code "180") (name "unconnected-(STM32F303VB-PF10-Pad11)") (class "Default")
      (node (ref "STM32F303VB") (pin "11") (pinfunction "PF10_11") (pintype "bidirectional"))
    )
    (net (code "181") (name "unconnected-(U1-IO4-Pad26)") (class "Default")
      (node (ref "U1") (pin "26") (pinfunction "IO4_26") (pintype "bidirectional"))
    )
    (net (code "182") (name "unconnected-(U1-IO5-Pad29)") (class "Default")
      (node (ref "U1") (pin "29") (pinfunction "IO5_29") (pintype "bidirectional"))
    )
    (net (code "183") (name "unconnected-(U1-IO17-Pad28)") (class "Default")
      (node (ref "U1") (pin "28") (pinfunction "IO17_28") (pintype "bidirectional"))
    )
    (net (code "184") (name "unconnected-(U1-IO18-Pad30)") (class "Default")
      (node (ref "U1") (pin "30") (pinfunction "IO18_30") (pintype "bidirectional"))
    )
    (net (code "185") (name "unconnected-(U1-IO19-Pad31)") (class "Default")
      (node (ref "U1") (pin "31") (pinfunction "IO19_31") (pintype "bidirectional"))
    )
    (net (code "186") (name "unconnected-(U1-IO23-Pad37)") (class "Default")
      (node (ref "U1") (pin "37") (pinfunction "IO23_37") (pintype "bidirectional"))
    )
    (net (code "187") (name "unconnected-(U1-IO25-Pad10)") (class "Default")
      (node (ref "U1") (pin "10") (pinfunction "IO25_10") (pintype "bidirectional"))
    )
    (net (code "188") (name "unconnected-(U1-IO26-Pad11)") (class "Default")
      (node (ref "U1") (pin "11") (pinfunction "IO26_11") (pintype "bidirectional"))
    )
    (net (code "189") (name "unconnected-(U1-IO27-Pad12)") (class "Default")
      (node (ref "U1") (pin "12") (pinfunction "IO27_12") (pintype "bidirectional"))
    )
    (net (code "190") (name "unconnected-(U1-IO32-Pad8)") (class "Default")
      (node (ref "U1") (pin "8") (pinfunction "IO32_8") (pintype "bidirectional"))
    )
    (net (code "191") (name "unconnected-(U1-IO33-Pad9)") (class "Default")
      (node (ref "U1") (pin "9") (pinfunction "IO33_9") (pintype "bidirectional"))
    )
    (net (code "192") (name "unconnected-(U1-IO34-Pad6)") (class "Default")
      (node (ref "U1") (pin "6") (pinfunction "IO34_6") (pintype "bidirectional"))
    )
    (net (code "193") (name "unconnected-(U1-IO35-Pad7)") (class "Default")
      (node (ref "U1") (pin "7") (pinfunction "IO35_7") (pintype "bidirectional"))
    )
    (net (code "194") (name "unconnected-(U1-SCL{slash}CLK-Pad20)") (class "Default")
      (node (ref "U1") (pin "20") (pinfunction "SCL/CLK_20") (pintype "bidirectional"))
    )
    (net (code "195") (name "unconnected-(U1-SCS{slash}CMD-Pad19)") (class "Default")
      (node (ref "U1") (pin "19") (pinfunction "SCS/CMD_19") (pintype "bidirectional"))
    )
    (net (code "196") (name "unconnected-(U1-SDI{slash}SD1-Pad22)") (class "Default")
      (node (ref "U1") (pin "22") (pinfunction "SDI/SD1_22") (pintype "bidirectional"))
    )
    (net (code "197") (name "unconnected-(U1-SDO{slash}SD0-Pad21)") (class "Default")
      (node (ref "U1") (pin "21") (pinfunction "SDO/SD0_21") (pintype "bidirectional"))
    )
    (net (code "198") (name "unconnected-(U1-SENSOR_VN-Pad5)") (class "Default")
      (node (ref "U1") (pin "5") (pinfunction "SENSOR_VN_5") (pintype "input"))
    )
    (net (code "199") (name "unconnected-(U1-SENSOR_VP-Pad4)") (class "Default")
      (node (ref "U1") (pin "4") (pinfunction "SENSOR_VP_4") (pintype "input"))
    )
    (net (code "200") (name "unconnected-(U1-SHD{slash}SD2-Pad17)") (class "Default")
      (node (ref "U1") (pin "17") (pinfunction "SHD/SD2_17") (pintype "bidirectional"))
    )
    (net (code "201") (name "unconnected-(U1-SWP{slash}SD3-Pad18)") (class "Default")
      (node (ref "U1") (pin "18") (pinfunction "SWP/SD3_18") (pintype "bidirectional"))
    )
    (net (code "202") (name "unconnected-(USB-C-CC1-PadA5)") (class "Default")
      (node (ref "USB-C") (pin "A5") (pinfunction "CC1_A5") (pintype "passive"))
    )
    (net (code "203") (name "unconnected-(USB-C-CC2-PadB5)") (class "Default")
      (node (ref "USB-C") (pin "B5") (pinfunction "CC2_B5") (pintype "passive"))
    )
    (net (code "204") (name "unconnected-(USB-C-RX1+-PadB11)") (class "Default")
      (node (ref "USB-C") (pin "B11") (pinfunction "RX1+_B11") (pintype "passive"))
    )
    (net (code "205") (name "unconnected-(USB-C-RX1--PadB10)") (class "Default")
      (node (ref "USB-C") (pin "B10") (pinfunction "RX1-_B10") (pintype "passive"))
    )
    (net (code "206") (name "unconnected-(USB-C-RX2+-PadA11)") (class "Default")
      (node (ref "USB-C") (pin "A11") (pinfunction "RX2+_A11") (pintype "passive"))
    )
    (net (code "207") (name "unconnected-(USB-C-RX2--PadA10)") (class "Default")
      (node (ref "USB-C") (pin "A10") (pinfunction "RX2-_A10") (pintype "passive"))
    )
    (net (code "208") (name "unconnected-(USB-C-SBU1-PadA8)") (class "Default")
      (node (ref "USB-C") (pin "A8") (pinfunction "SBU1_A8") (pintype "passive"))
    )
    (net (code "209") (name "unconnected-(USB-C-SBU2-PadB8)") (class "Default")
      (node (ref "USB-C") (pin "B8") (pinfunction "SBU2_B8") (pintype "passive"))
    )
    (net (code "210") (name "unconnected-(USB-C-TX1+-PadA2)") (class "Default")
      (node (ref "USB-C") (pin "A2") (pinfunction "TX1+_A2") (pintype "passive"))
    )
    (net (code "211") (name "unconnected-(USB-C-TX1--PadA3)") (class "Default")
      (node (ref "USB-C") (pin "A3") (pinfunction "TX1-_A3") (pintype "passive"))
    )
    (net (code "212") (name "unconnected-(USB-C-TX2+-PadB2)") (class "Default")
      (node (ref "USB-C") (pin "B2") (pinfunction "TX2+_B2") (pintype "passive"))
    )
    (net (code "213") (name "unconnected-(USB-C-TX2--PadB3)") (class "Default")
      (node (ref "USB-C") (pin "B3") (pinfunction "TX2-_B3") (pintype "passive"))
    )
  )
)
